# Cing_MainBoard.net
KiCad netlist of a schematic drawn in EAGLE
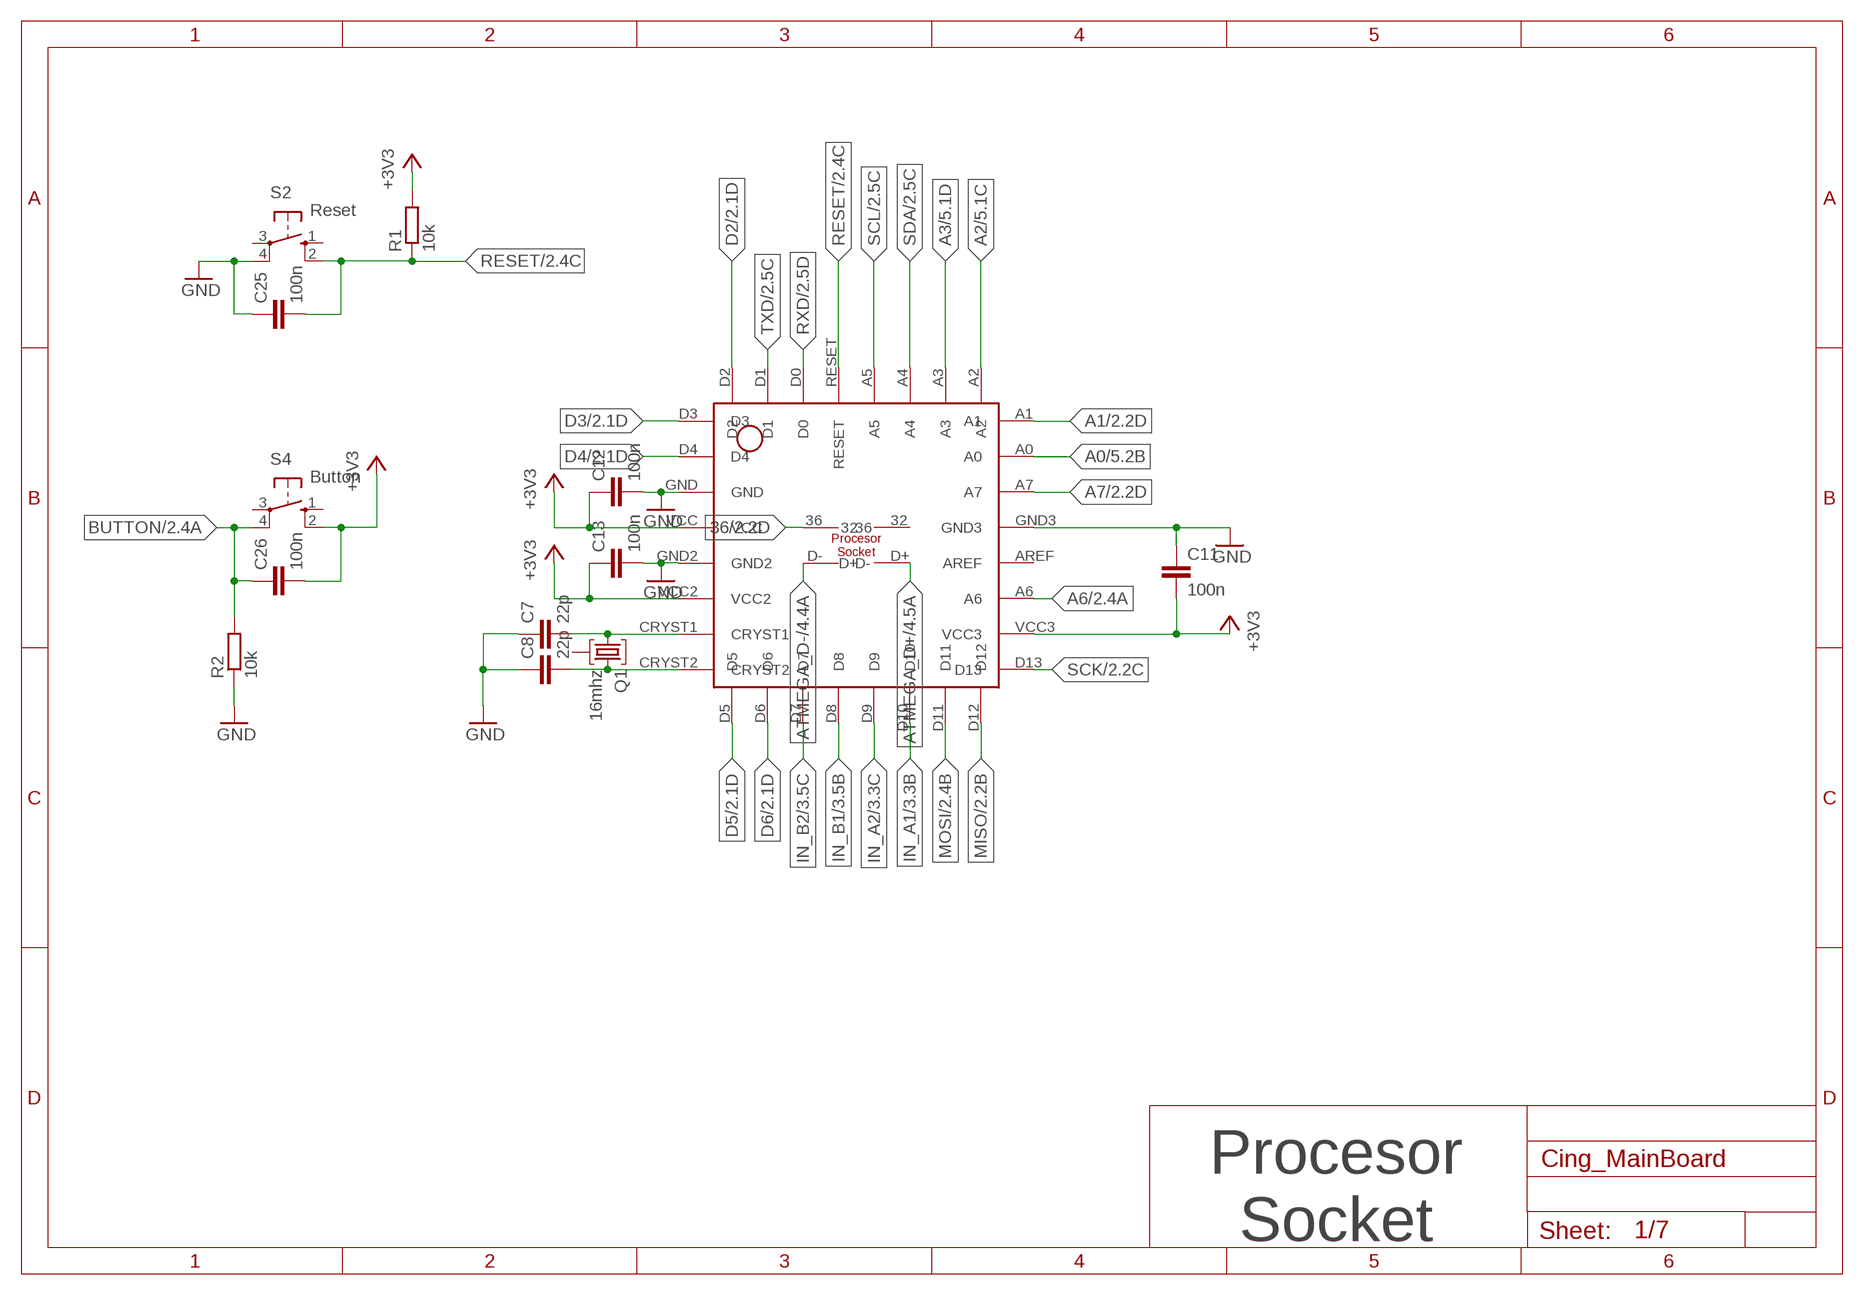
[diagram p0: schematic, sheet 1]
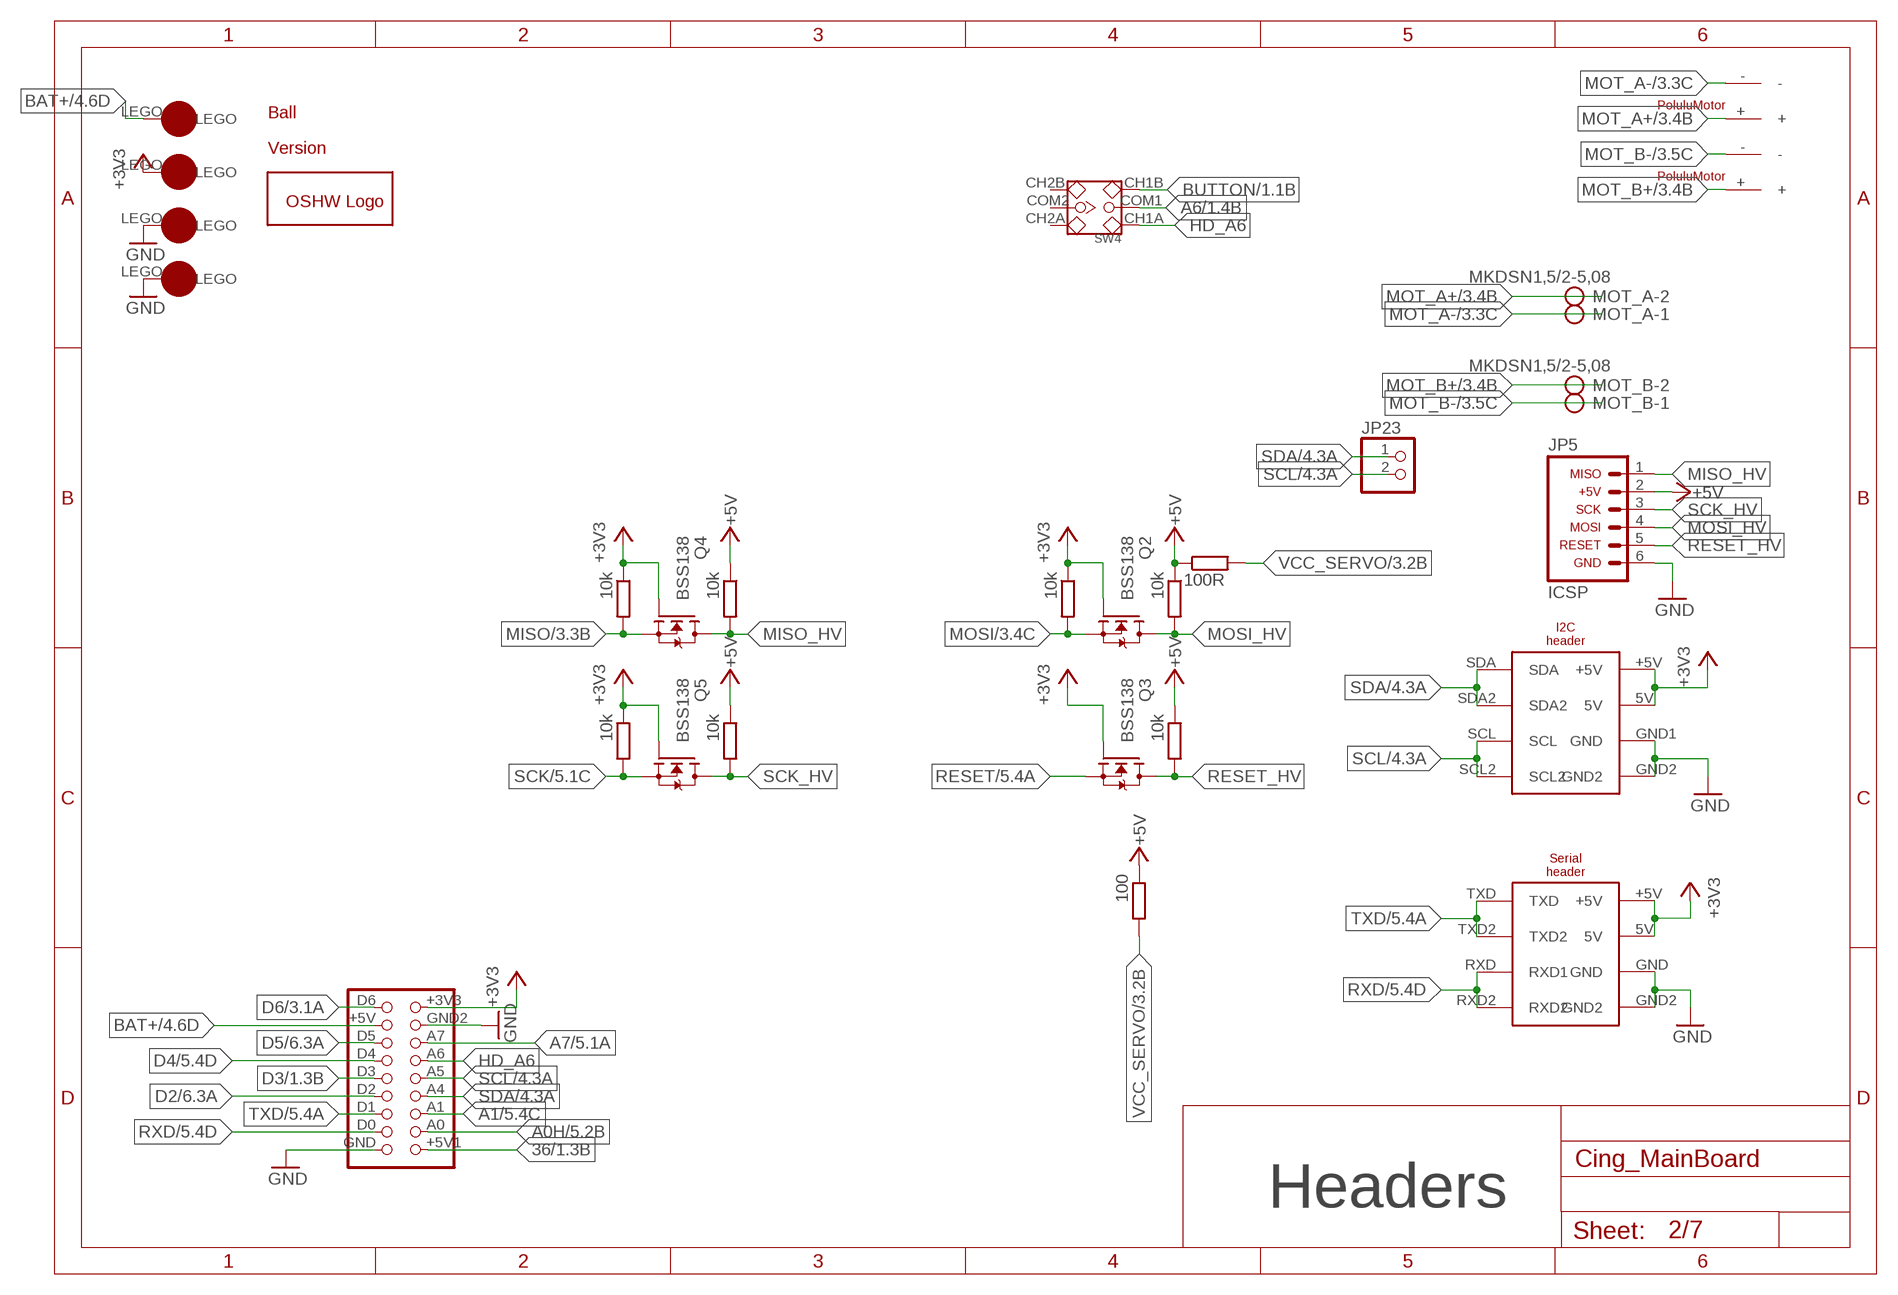
[diagram p1: schematic, sheet 2]
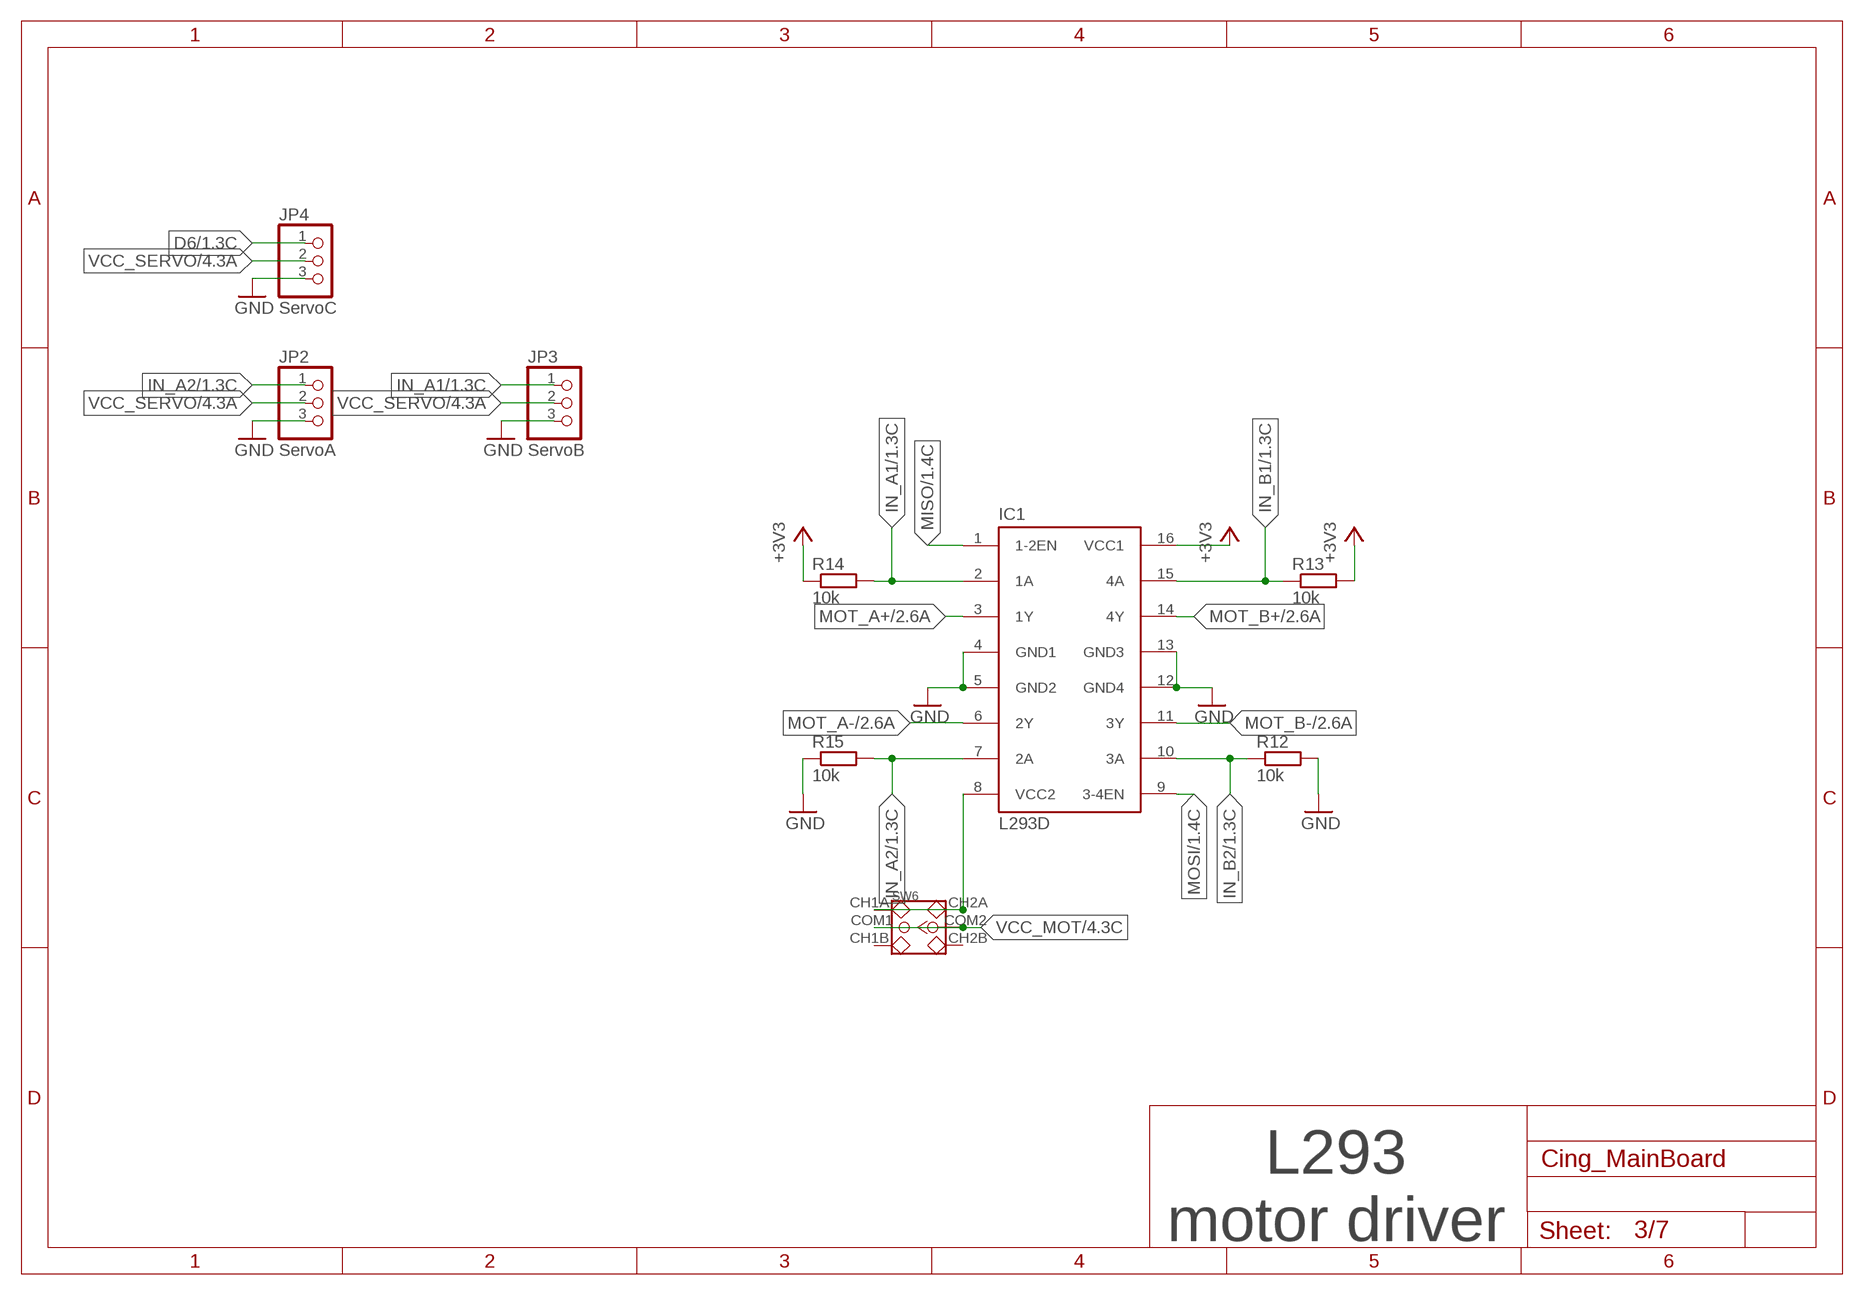
[diagram p2: schematic, sheet 3]
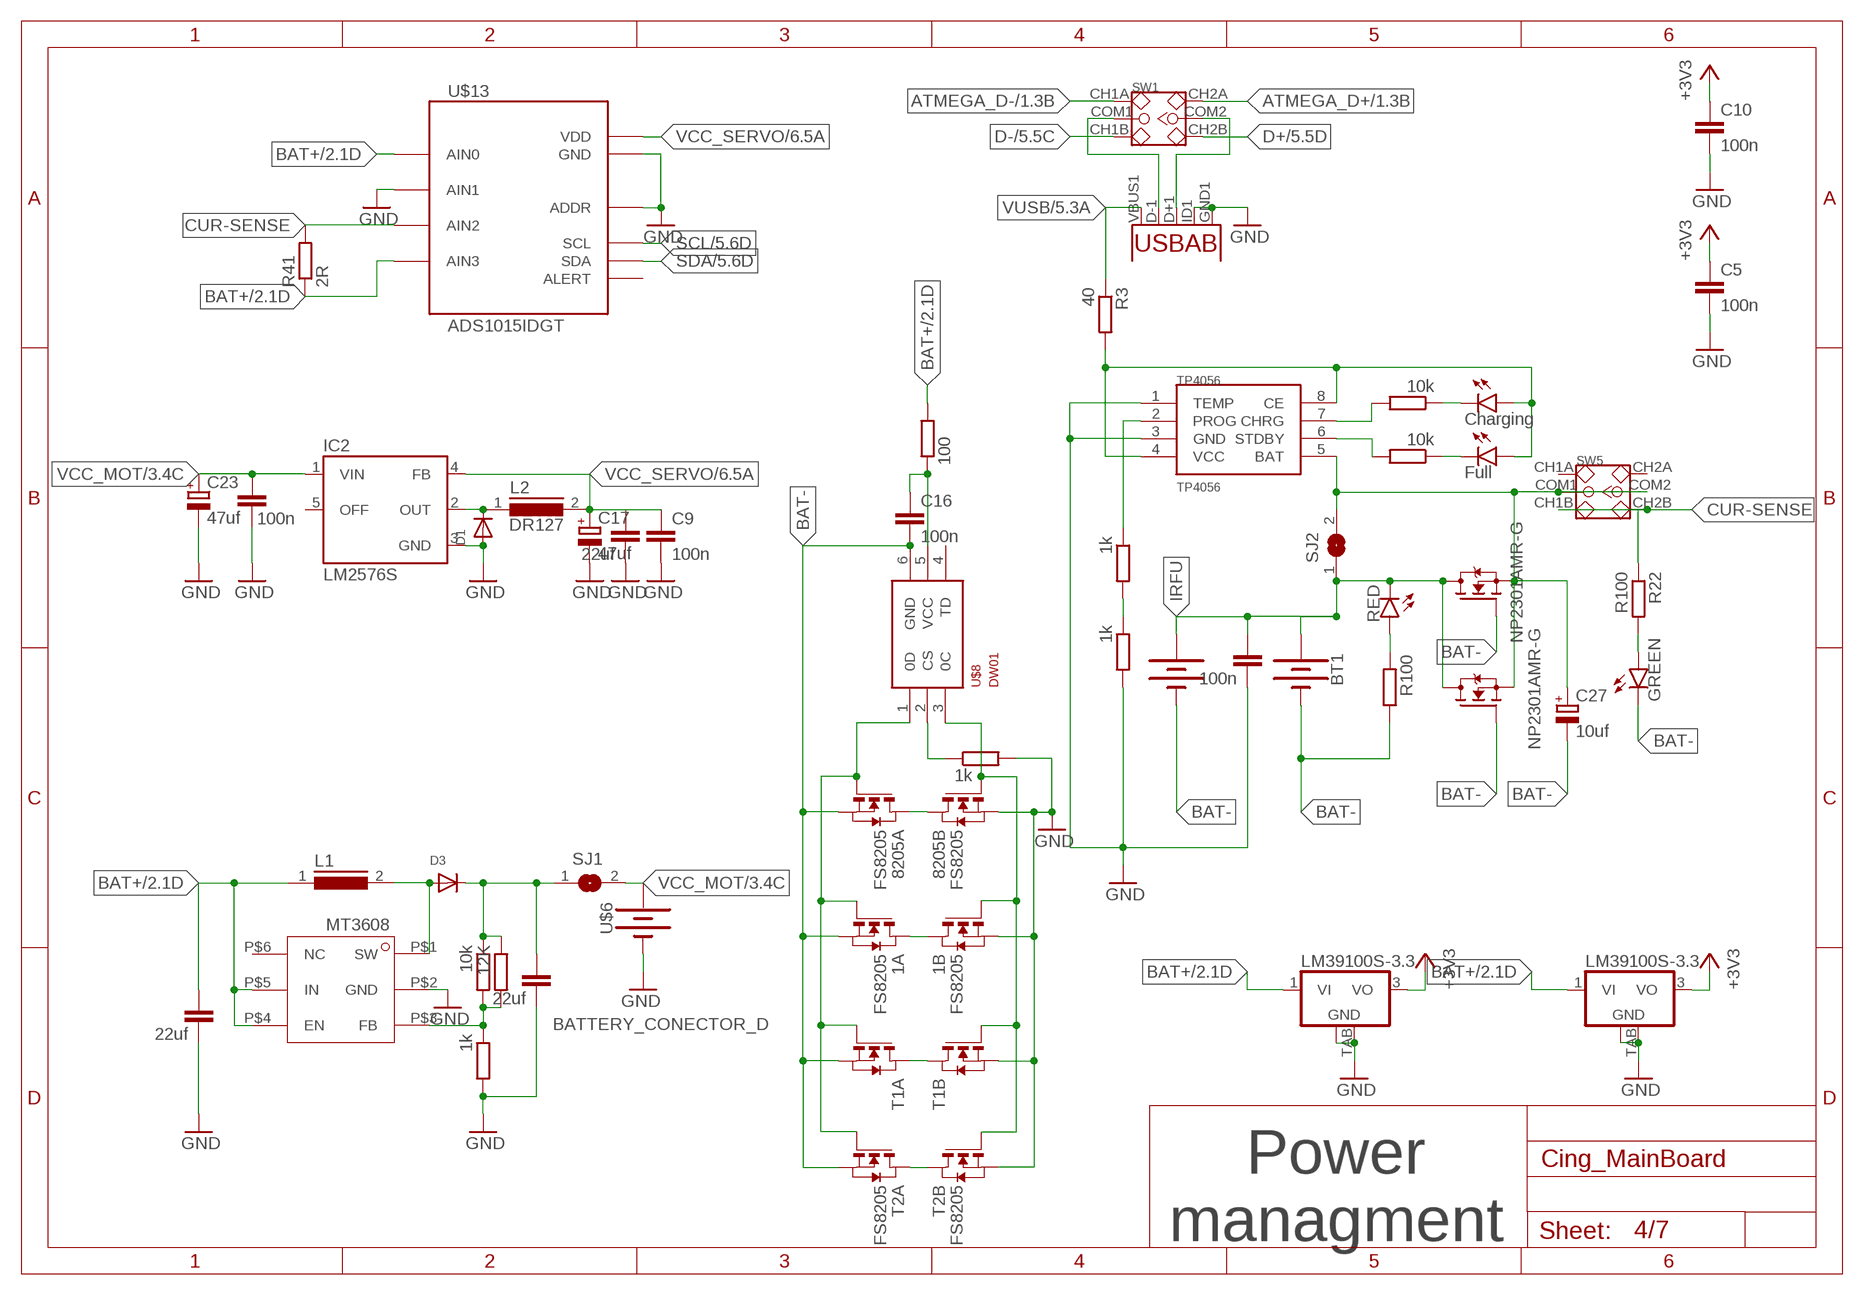
[diagram p3: schematic, sheet 4]
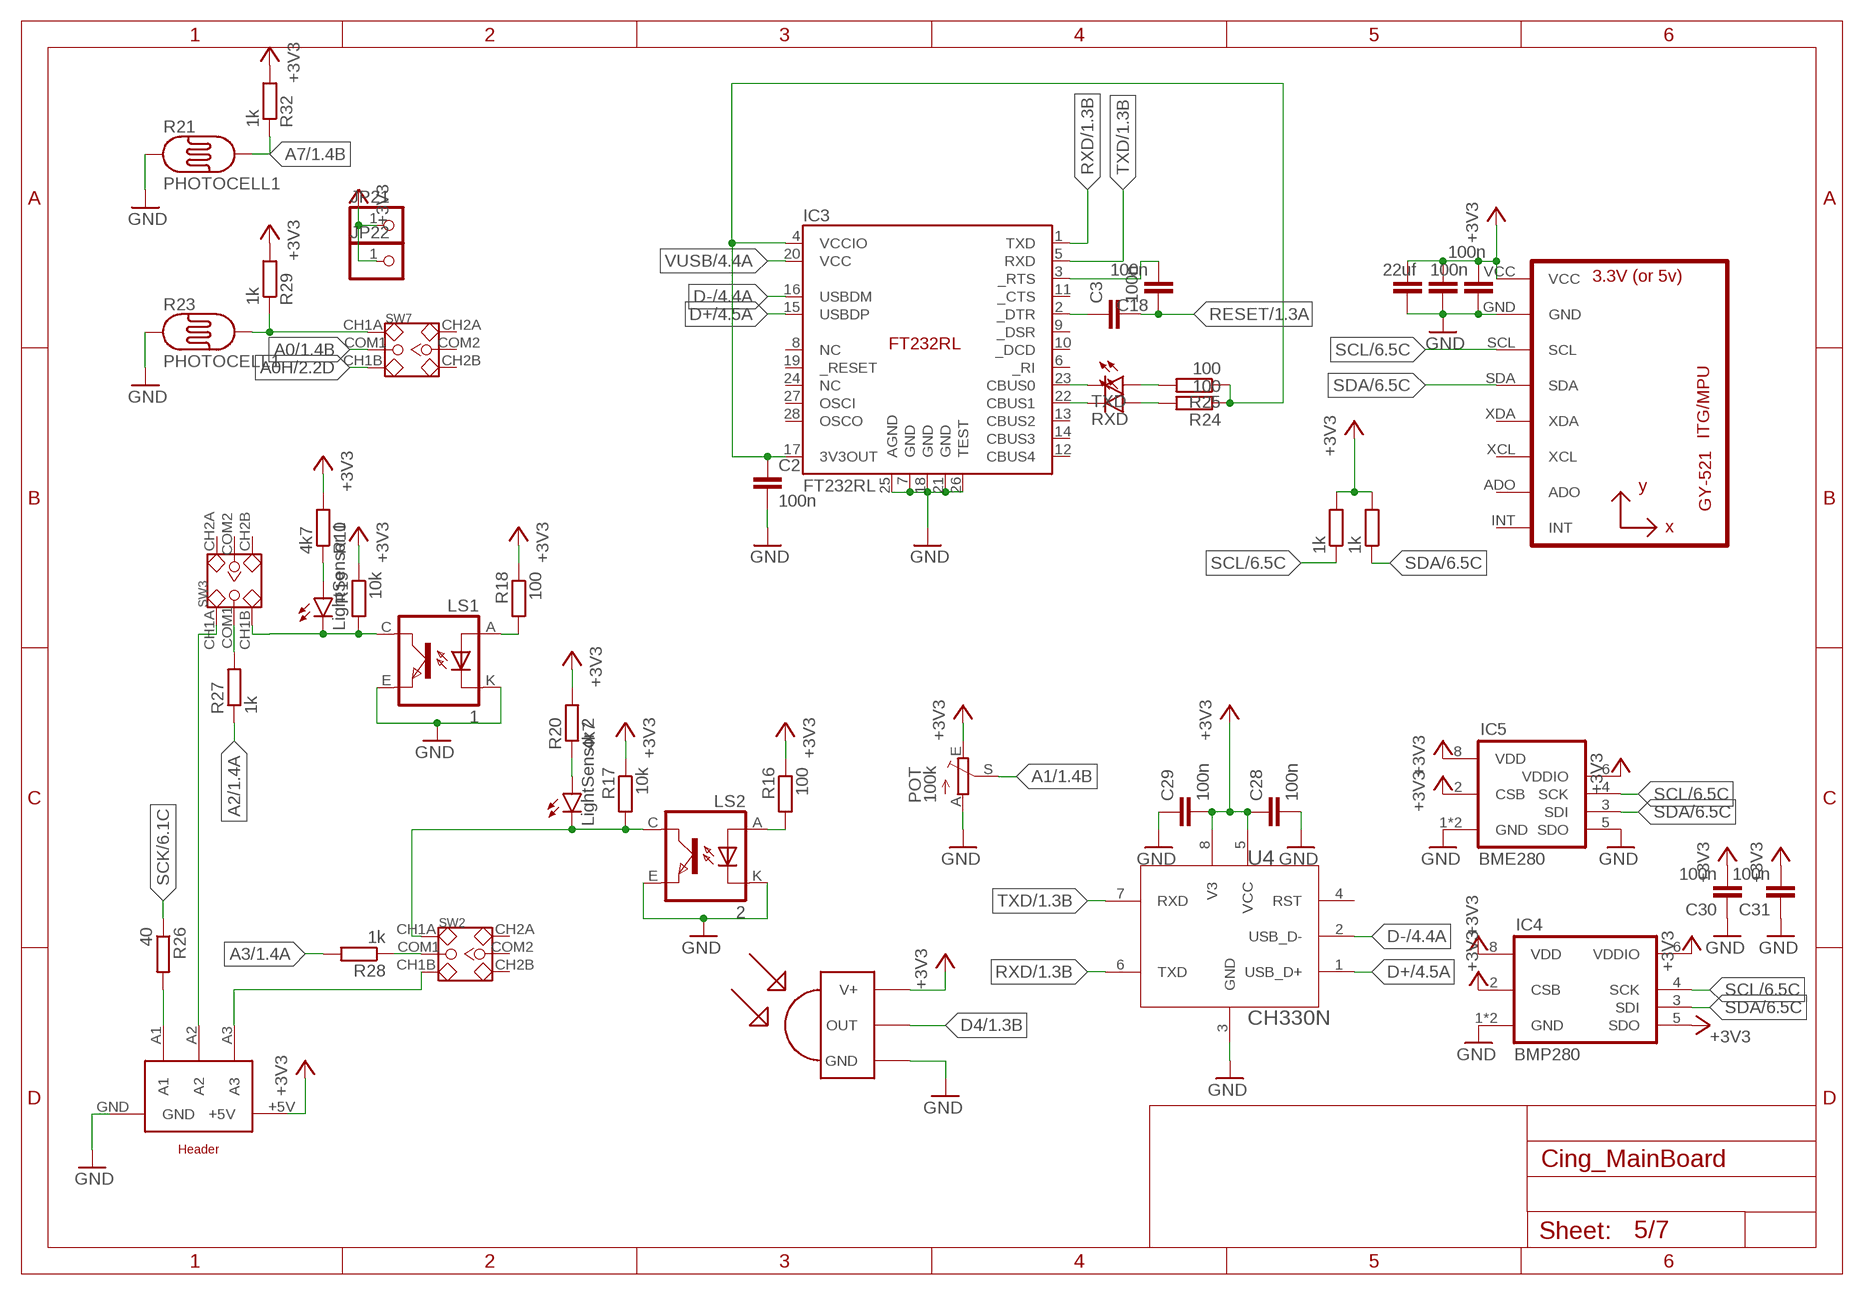
[diagram p4: schematic, sheet 5]
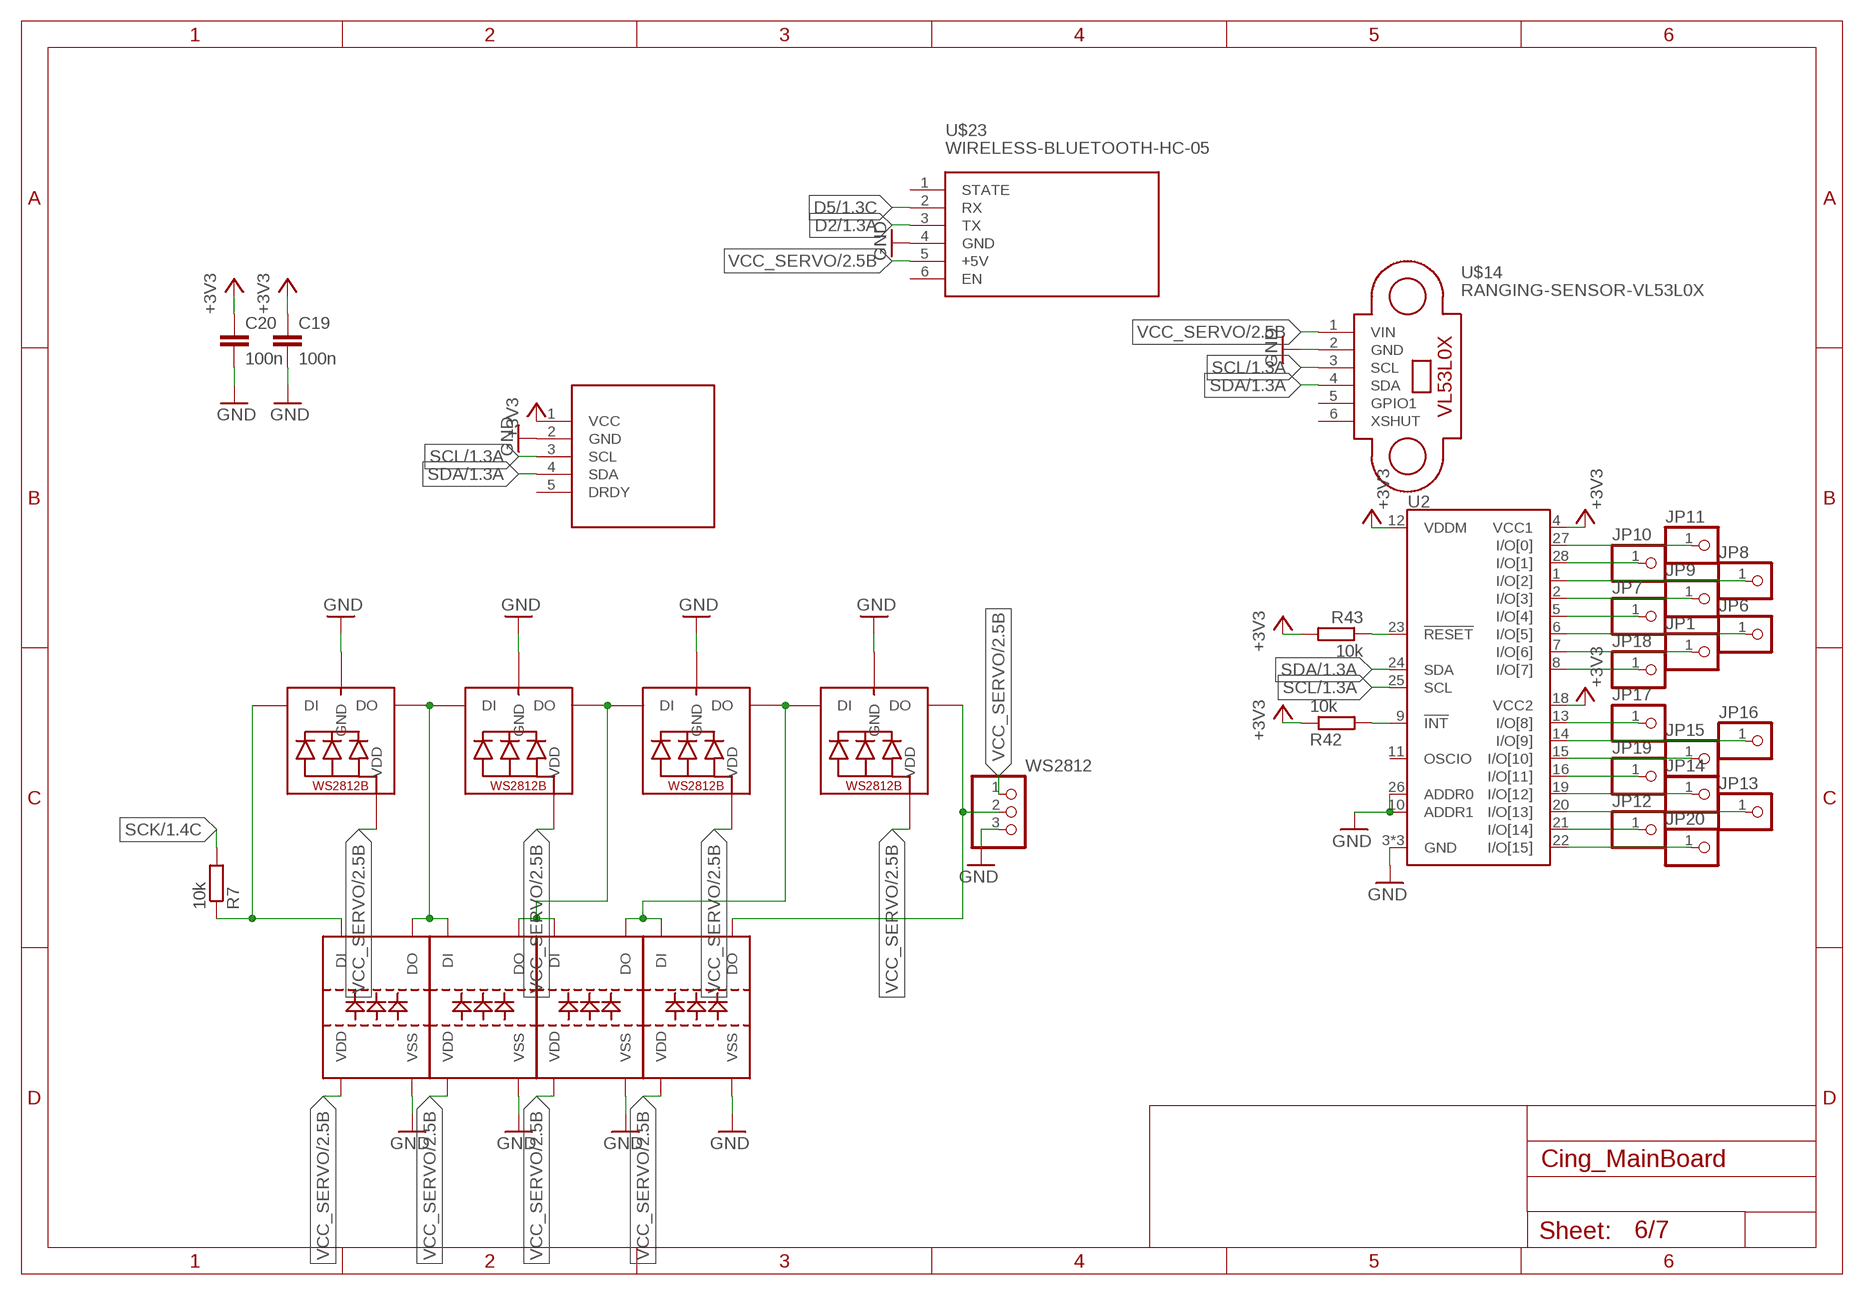
[diagram p5: schematic, sheet 6]
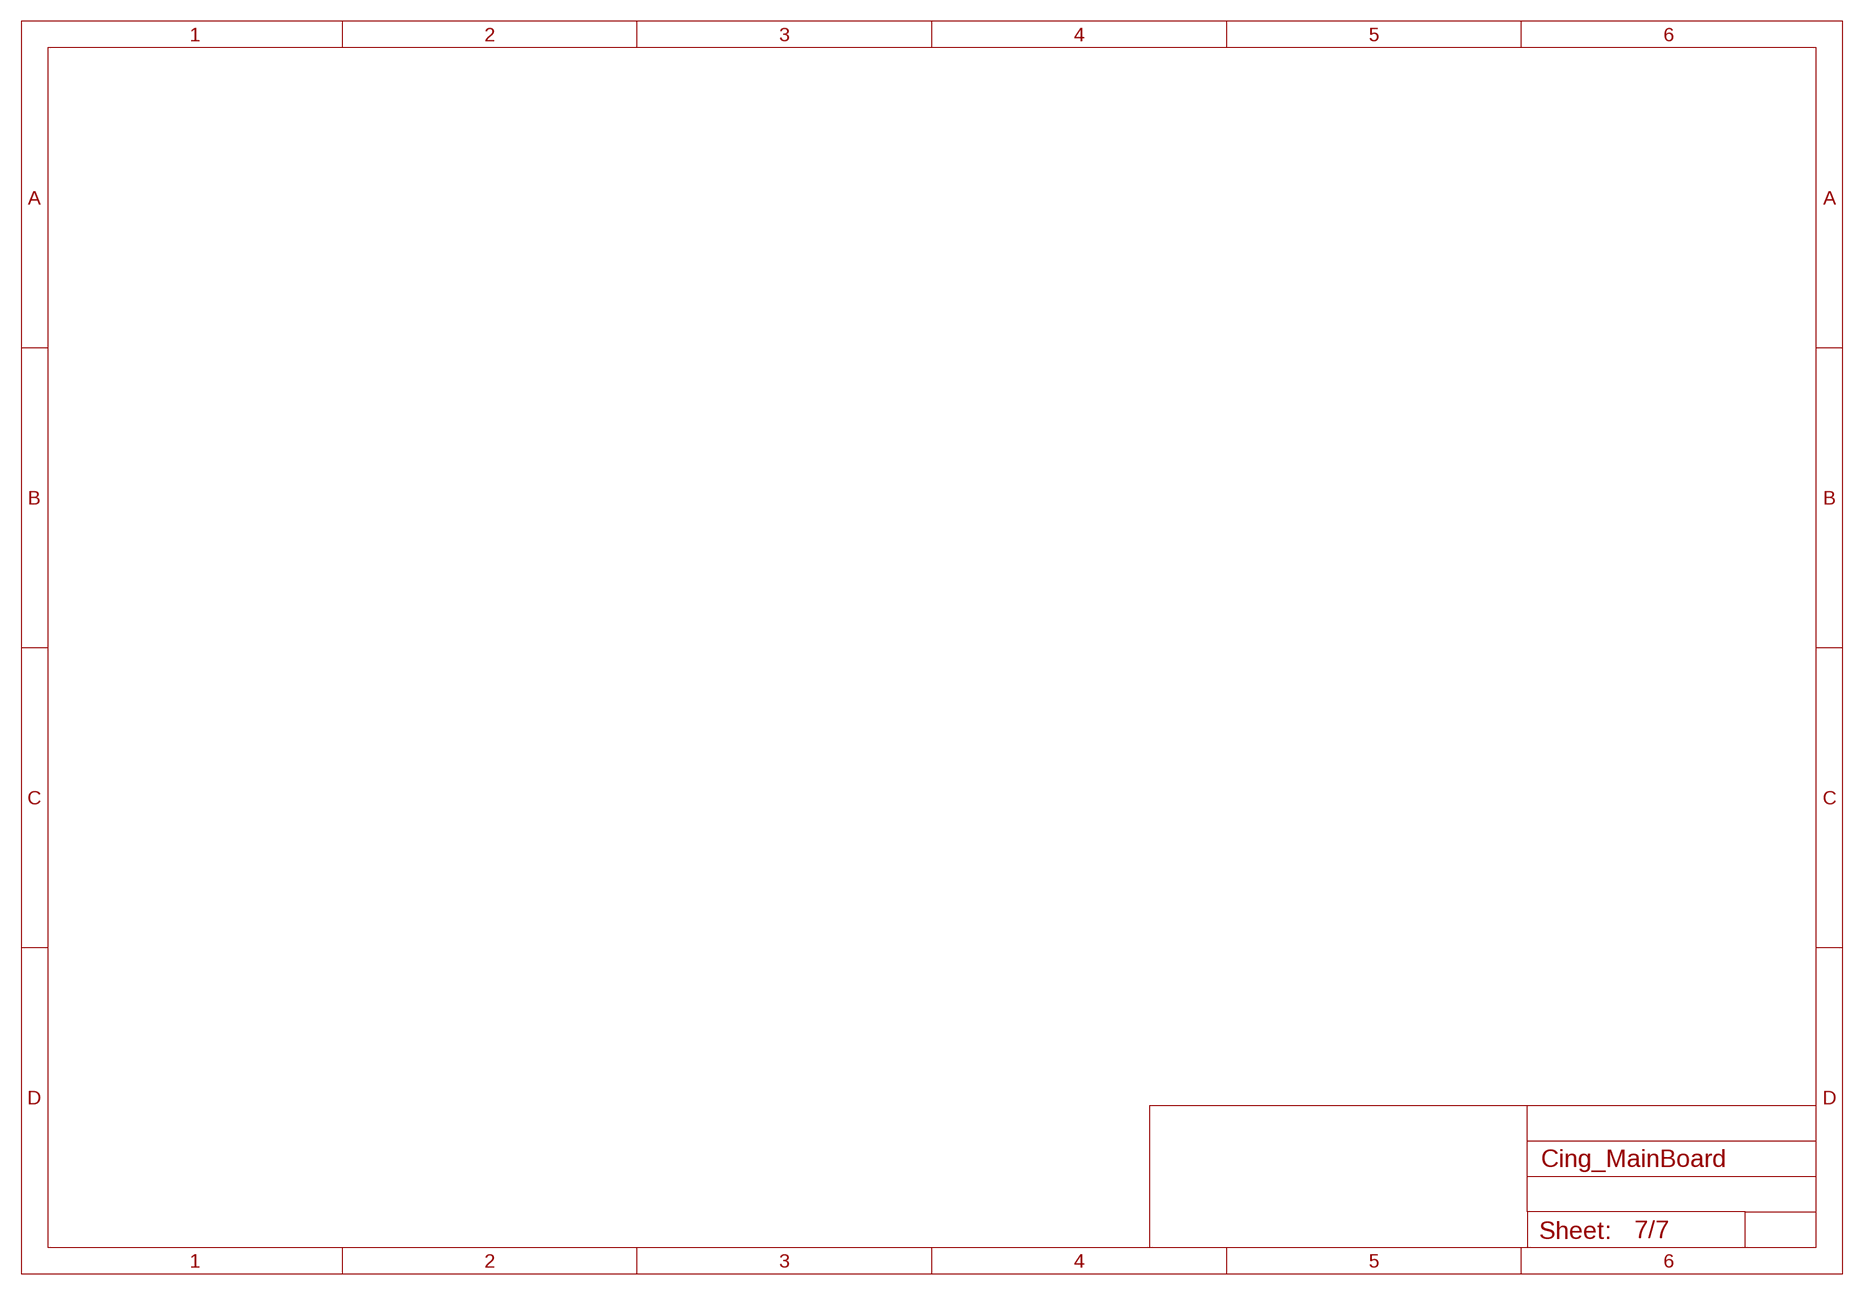
[diagram p6: schematic, sheet 7]

(export (version "E")
  (design (tool "Eeschema 10.0.6"))
  (components
    (comp (ref "C7")
      (value "22p")
      (footprint "eagle-import:C1206")
      (libsource (lib "eagle-import") (part "C-EUC1206"))
    )
    (comp (ref "C8")
      (value "22p")
      (footprint "eagle-import:C1206")
      (libsource (lib "eagle-import") (part "C-EUC1206"))
    )
    (comp (ref "C11")
      (value "100n")
      (footprint "eagle-import:C1206")
      (libsource (lib "eagle-import") (part "C-EUC1206"))
    )
    (comp (ref "C12")
      (value "100n")
      (footprint "eagle-import:C1206")
      (libsource (lib "eagle-import") (part "C-EUC1206"))
    )
    (comp (ref "C13")
      (value "100n")
      (footprint "eagle-import:C1206")
      (libsource (lib "eagle-import") (part "C-EUC1206"))
    )
    (comp (ref "C25")
      (value "100n")
      (footprint "eagle-import:C1206")
      (libsource (lib "eagle-import") (part "C-EUC1206"))
    )
    (comp (ref "C26")
      (value "100n")
      (footprint "eagle-import:C1206")
      (libsource (lib "eagle-import") (part "C-EUC1206"))
    )
    (comp (ref "Q1")
      (value "16mhz")
      (footprint "eagle-import:HC49U")
      (libsource (lib "eagle-import") (part "12M10AHC49HT"))
    )
    (comp (ref "R1")
      (value "10k")
      (footprint "eagle-import:R1206")
      (libsource (lib "eagle-import") (part "R-EU_R1206"))
    )
    (comp (ref "R2")
      (value "10k")
      (footprint "eagle-import:R1206")
      (libsource (lib "eagle-import") (part "R-EU_R1206"))
    )
    (comp (ref "S2")
      (value "Reset")
      (footprint "eagle-import:B3F-10XX")
      (fields (field (name "MPN") "B3F-1000"))
      (libsource (lib "eagle-import") (part "10-XX"))
    )
    (comp (ref "S4")
      (value "Button")
      (footprint "eagle-import:B3F-10XX")
      (fields (field (name "MPN") "B3F-1000"))
      (libsource (lib "eagle-import") (part "10-XX"))
    )
    (comp (ref "U$1")
      (value "PROCESSOR-SOCKET_PCB")
      (footprint "eagle-import:PROCESSOR-SOCKET_PCB")
      (libsource (lib "eagle-import") (part "PROCESSOR-SOCKET_PCB"))
    )
    (comp (ref "C2")
      (value "100n")
      (footprint "eagle-import:C1206")
      (libsource (lib "eagle-import") (part "C-EUC1206"))
    )
    (comp (ref "C3")
      (value "100n")
      (footprint "eagle-import:C1206")
      (libsource (lib "eagle-import") (part "C-EUC1206"))
    )
    (comp (ref "C6")
      (value "100n")
      (footprint "eagle-import:C1206")
      (libsource (lib "eagle-import") (part "C-EUC1206"))
    )
    (comp (ref "C18")
      (value "100n")
      (footprint "eagle-import:C1206")
      (libsource (lib "eagle-import") (part "C-EUC1206"))
    )
    (comp (ref "C21")
      (value "100n")
      (footprint "eagle-import:C1206")
      (libsource (lib "eagle-import") (part "C-EUC1206"))
    )
    (comp (ref "C22")
      (value "22uf")
      (footprint "eagle-import:C1206")
      (libsource (lib "eagle-import") (part "C-EUC1206"))
    )
    (comp (ref "C28")
      (value "100n")
      (footprint "eagle-import:C1206")
      (libsource (lib "eagle-import") (part "C-EUC1206"))
    )
    (comp (ref "C29")
      (value "100n")
      (footprint "eagle-import:C1206")
      (libsource (lib "eagle-import") (part "C-EUC1206"))
    )
    (comp (ref "C30")
      (value "100n")
      (footprint "eagle-import:C1206")
      (libsource (lib "eagle-import") (part "C-EUC1206"))
    )
    (comp (ref "C31")
      (value "100n")
      (footprint "eagle-import:C1206")
      (libsource (lib "eagle-import") (part "C-EUC1206"))
    )
    (comp (ref "IC3")
      (value "FT232RL")
      (footprint "eagle-import:FT232RL")
      (libsource (lib "eagle-import") (part "FT232RL"))
    )
    (comp (ref "IC4")
      (value "BMP280")
      (footprint "eagle-import:BMP280")
      (libsource (lib "eagle-import") (part "BMP280"))
    )
    (comp (ref "IC5")
      (value "BME280")
      (footprint "eagle-import:BME280")
      (libsource (lib "eagle-import") (part "BME280"))
    )
    (comp (ref "JP21")
      (value "PINHD-1X1")
      (footprint "eagle-import:1X01")
      (libsource (lib "eagle-import") (part "PINHD-1X1"))
    )
    (comp (ref "JP22")
      (value "PINHD-1X1")
      (footprint "eagle-import:1X01")
      (libsource (lib "eagle-import") (part "PINHD-1X1"))
    )
    (comp (ref "LED3")
      (value "RXD")
      (footprint "eagle-import:1206")
      (libsource (lib "eagle-import") (part "LEDSMT1206"))
    )
    (comp (ref "LS1")
      (value "1")
      (footprint "eagle-import:TCRT5000")
      (libsource (lib "eagle-import") (part "TCRT5000"))
    )
    (comp (ref "LS2")
      (value "2")
      (footprint "eagle-import:TCRT5000")
      (libsource (lib "eagle-import") (part "TCRT5000"))
    )
    (comp (ref "POT")
      (value "100k")
      (footprint "eagle-import:RJ9W")
      (libsource (lib "eagle-import") (part "TRIM_EU-RJ9W"))
    )
    (comp (ref "R10")
      (value "4k7")
      (footprint "eagle-import:R1206")
      (libsource (lib "eagle-import") (part "R-EU_R1206"))
    )
    (comp (ref "R16")
      (value "100")
      (footprint "eagle-import:R1206")
      (libsource (lib "eagle-import") (part "R-EU_R1206"))
    )
    (comp (ref "R17")
      (value "10k")
      (footprint "eagle-import:R1206")
      (libsource (lib "eagle-import") (part "R-EU_R1206"))
    )
    (comp (ref "R18")
      (value "100")
      (footprint "eagle-import:R1206")
      (libsource (lib "eagle-import") (part "R-EU_R1206"))
    )
    (comp (ref "R19")
      (value "10k")
      (footprint "eagle-import:R1206")
      (libsource (lib "eagle-import") (part "R-EU_R1206"))
    )
    (comp (ref "R20")
      (value "4k7")
      (footprint "eagle-import:R1206")
      (libsource (lib "eagle-import") (part "R-EU_R1206"))
    )
    (comp (ref "R21")
      (value "PHOTOCELL1")
      (footprint "eagle-import:LDR_OFFBOARD")
      (libsource (lib "eagle-import") (part "PHOTOCELL1"))
    )
    (comp (ref "R23")
      (value "PHOTOCELL1")
      (footprint "eagle-import:LDR_OFFBOARD")
      (libsource (lib "eagle-import") (part "PHOTOCELL1"))
    )
    (comp (ref "R24")
      (value "100")
      (footprint "eagle-import:R1206")
      (libsource (lib "eagle-import") (part "R-EU_R1206"))
    )
    (comp (ref "R25")
      (value "100")
      (footprint "eagle-import:R1206")
      (libsource (lib "eagle-import") (part "R-EU_R1206"))
    )
    (comp (ref "R26")
      (value "40")
      (footprint "eagle-import:R1206")
      (libsource (lib "eagle-import") (part "R-EU_R1206"))
    )
    (comp (ref "R27")
      (value "1k")
      (footprint "eagle-import:R1206")
      (libsource (lib "eagle-import") (part "R-EU_R1206"))
    )
    (comp (ref "R28")
      (value "1k")
      (footprint "eagle-import:R1206")
      (libsource (lib "eagle-import") (part "R-EU_R1206"))
    )
    (comp (ref "R29")
      (value "1k")
      (footprint "eagle-import:R1206")
      (libsource (lib "eagle-import") (part "R-EU_R1206"))
    )
    (comp (ref "R30")
      (value "1k")
      (footprint "eagle-import:R1206")
      (libsource (lib "eagle-import") (part "R-EU_R1206"))
    )
    (comp (ref "R31")
      (value "1k")
      (footprint "eagle-import:R1206")
      (libsource (lib "eagle-import") (part "R-EU_R1206"))
    )
    (comp (ref "R32")
      (value "1k")
      (footprint "eagle-import:R1206")
      (libsource (lib "eagle-import") (part "R-EU_R1206"))
    )
    (comp (ref "SW2")
      (value "USB_SWITCH")
      (footprint "eagle-import:USB_SWITCH")
      (libsource (lib "eagle-import") (part "USB_SWITCH"))
    )
    (comp (ref "SW3")
      (value "USB_SWITCH")
      (footprint "eagle-import:USB_SWITCH")
      (libsource (lib "eagle-import") (part "USB_SWITCH"))
    )
    (comp (ref "SW7")
      (value "USB_SWITCH")
      (footprint "eagle-import:USB_SWITCH")
      (libsource (lib "eagle-import") (part "USB_SWITCH"))
    )
    (comp (ref "TSOP4838")
      (value "TSOP4838")
      (footprint "eagle-import:TSOP18XX")
      (libsource (lib "eagle-import") (part "TSOP4838"))
    )
    (comp (ref "TXD")
      (value "TXD")
      (footprint "eagle-import:1206")
      (libsource (lib "eagle-import") (part "LEDSMT1206"))
    )
    (comp (ref "TXD1")
      (value "LightSensor 1")
      (footprint "eagle-import:1206")
      (libsource (lib "eagle-import") (part "LEDSMT1206"))
    )
    (comp (ref "TXD2")
      (value "LightSensor 2")
      (footprint "eagle-import:1206")
      (libsource (lib "eagle-import") (part "LEDSMT1206"))
    )
    (comp (ref "U$12")
      (value "CONNECTOR_1X5")
      (footprint "eagle-import:CONNECTOR_1X5")
      (libsource (lib "eagle-import") (part "CONNECTOR_1X5"))
    )
    (comp (ref "U3")
      (value "MPU-6050MPU6050")
      (footprint "eagle-import:MPU-6050")
      (libsource (lib "eagle-import") (part "MPU-6050MPU6050"))
    )
    (comp (ref "U4")
      (value "CH330N")
      (footprint "eagle-import:SOIC-8N")
      (fields
        (field (name "DIGI-KEY_PART") "LM555CMFS-ND")
        (field (name "MANUFACTURER") "ON Semiconductor")
        (field (name "MPN") "LM555CM")
        (field (name "CREATED_BY") "PCBLayout.com")
      )
      (libsource (lib "eagle-import") (part "CH330N"))
    )
    (comp (ref "1")
      (value "FS8205")
      (footprint "eagle-import:TSSOP-8")
      (libsource (lib "eagle-import") (part "DMN3024LSD"))
    )
    (comp (ref "8205")
      (value "FS8205")
      (footprint "eagle-import:TSSOP-8")
      (libsource (lib "eagle-import") (part "DMN3024LSD"))
    )
    (comp (ref "BT1")
      (value "BATTERY-AA_KIT")
      (footprint "eagle-import:BATTERY-AA-KIT")
      (libsource (lib "eagle-import") (part "BATTERY-AA_KIT"))
    )
    (comp (ref "C1")
      (value "100n")
      (footprint "eagle-import:C1206")
      (libsource (lib "eagle-import") (part "C-EUC1206"))
    )
    (comp (ref "C4")
      (value "22uf")
      (footprint "eagle-import:C1206")
      (libsource (lib "eagle-import") (part "C-EUC1206"))
    )
    (comp (ref "C5")
      (value "100n")
      (footprint "eagle-import:C1206")
      (libsource (lib "eagle-import") (part "C-EUC1206"))
    )
    (comp (ref "C9")
      (value "100n")
      (footprint "eagle-import:C1206")
      (libsource (lib "eagle-import") (part "C-EUC1206"))
    )
    (comp (ref "C10")
      (value "100n")
      (footprint "eagle-import:C1206")
      (libsource (lib "eagle-import") (part "C-EUC1206"))
    )
    (comp (ref "C14")
      (value "22uf")
      (footprint "eagle-import:C1206")
      (libsource (lib "eagle-import") (part "C-EUC1206"))
    )
    (comp (ref "C15")
      (value "22uf")
      (footprint "eagle-import:C1206")
      (libsource (lib "eagle-import") (part "C-EUC1206"))
    )
    (comp (ref "C16")
      (value "100n")
      (footprint "eagle-import:C1206")
      (libsource (lib "eagle-import") (part "C-EUC1206"))
    )
    (comp (ref "C17")
      (value "47uf")
      (footprint "eagle-import:153CLV-0505")
      (libsource (lib "eagle-import") (part "CPOL-EU153CLV-0505"))
    )
    (comp (ref "C23")
      (value "47uf")
      (footprint "eagle-import:153CLV-0505")
      (libsource (lib "eagle-import") (part "CPOL-EU153CLV-0505"))
    )
    (comp (ref "C24")
      (value "100n")
      (footprint "eagle-import:C1206")
      (libsource (lib "eagle-import") (part "C-EUC1206"))
    )
    (comp (ref "C27")
      (value "10uf")
      (footprint "eagle-import:153CLV-0505")
      (libsource (lib "eagle-import") (part "CPOL-EU153CLV-0505"))
    )
    (comp (ref "D1")
      (value "DIODESMA")
      (footprint "eagle-import:SMADIODE")
      (libsource (lib "eagle-import") (part "DIODESMA"))
    )
    (comp (ref "D3")
      (value "DIODESMA")
      (footprint "eagle-import:SMADIODE")
      (libsource (lib "eagle-import") (part "DIODESMA"))
    )
    (comp (ref "IC2")
      (value "LM2576S")
      (footprint "eagle-import:TO263-5")
      (libsource (lib "eagle-import") (part "LM2576S"))
    )
    (comp (ref "L1")
      (value "DR125")
      (footprint "eagle-import:DR125")
      (libsource (lib "eagle-import") (part "DR125"))
    )
    (comp (ref "L2")
      (value "DR127")
      (footprint "eagle-import:DR127")
      (libsource (lib "eagle-import") (part "DR127"))
    )
    (comp (ref "LED1")
      (value "Charging")
      (footprint "eagle-import:1206")
      (libsource (lib "eagle-import") (part "LEDSMT1206"))
    )
    (comp (ref "ON")
      (value "GREEN")
      (footprint "eagle-import:1206")
      (libsource (lib "eagle-import") (part "LEDSMT1206"))
    )
    (comp (ref "Q6")
      (value "NP2301AMR-G")
      (footprint "eagle-import:SOT23")
      (fields (field (name "MF") "Fairchild") (field (name "MPN") "BSS138"))
      (libsource (lib "eagle-import") (part "NP2301AMR-G"))
    )
    (comp (ref "Q7")
      (value "NP2301AMR-G")
      (footprint "eagle-import:SOT23")
      (fields (field (name "MF") "Fairchild") (field (name "MPN") "BSS138"))
      (libsource (lib "eagle-import") (part "NP2301AMR-G"))
    )
    (comp (ref "R3")
      (value "40")
      (footprint "eagle-import:R1206")
      (libsource (lib "eagle-import") (part "R-EU_R1206"))
    )
    (comp (ref "R4")
      (value "1k")
      (footprint "eagle-import:R1206")
      (libsource (lib "eagle-import") (part "R-EU_R1206"))
    )
    (comp (ref "R5")
      (value "10k")
      (footprint "eagle-import:R1206")
      (libsource (lib "eagle-import") (part "R-EU_R1206"))
    )
    (comp (ref "R6")
      (value "R100")
      (footprint "eagle-import:R1206")
      (libsource (lib "eagle-import") (part "R-EU_R1206"))
    )
    (comp (ref "R8")
      (value "1k")
      (footprint "eagle-import:R1206")
      (libsource (lib "eagle-import") (part "R-EU_R1206"))
    )
    (comp (ref "R9")
      (value "10k")
      (footprint "eagle-import:R1206")
      (libsource (lib "eagle-import") (part "R-EU_R1206"))
    )
    (comp (ref "R11")
      (value "10k")
      (footprint "eagle-import:R1206")
      (libsource (lib "eagle-import") (part "R-EU_R1206"))
    )
    (comp (ref "R22")
      (value "R100")
      (footprint "eagle-import:R1206")
      (libsource (lib "eagle-import") (part "R-EU_R1206"))
    )
    (comp (ref "R41")
      (value "2R")
      (footprint "eagle-import:R1206")
      (libsource (lib "eagle-import") (part "R-EU_R1206"))
    )
    (comp (ref "R46")
      (value "1k")
      (footprint "eagle-import:R1206")
      (libsource (lib "eagle-import") (part "R-EU_R1206"))
    )
    (comp (ref "R47")
      (value "1k")
      (footprint "eagle-import:R1206")
      (libsource (lib "eagle-import") (part "R-EU_R1206"))
    )
    (comp (ref "R48")
      (value "100")
      (footprint "eagle-import:R1206")
      (libsource (lib "eagle-import") (part "R-EU_R1206"))
    )
    (comp (ref "R49")
      (value "12K")
      (footprint "eagle-import:R1206")
      (libsource (lib "eagle-import") (part "R-EU_R1206"))
    )
    (comp (ref "REV")
      (value "RED")
      (footprint "eagle-import:1206")
      (libsource (lib "eagle-import") (part "LEDSMT1206"))
    )
    (comp (ref "SJ1")
      (value "SJW")
      (footprint "eagle-import:SJW")
      (libsource (lib "eagle-import") (part "SJW"))
    )
    (comp (ref "SJ2") (value "SJ") (footprint "eagle-import:SJ") (libsource (lib "eagle-import") (part "SJ")))
    (comp (ref "SW1")
      (value "USB_SWITCH")
      (footprint "eagle-import:USB_SWITCH")
      (libsource (lib "eagle-import") (part "USB_SWITCH"))
    )
    (comp (ref "SW5")
      (value "USB_SWITCH")
      (footprint "eagle-import:USB_SWITCH")
      (libsource (lib "eagle-import") (part "USB_SWITCH"))
    )
    (comp (ref "T1")
      (value "FS8205")
      (footprint "eagle-import:TSSOP-8")
      (libsource (lib "eagle-import") (part "DMN3024LSD"))
    )
    (comp (ref "T2")
      (value "FS8205")
      (footprint "eagle-import:TSSOP-8")
      (libsource (lib "eagle-import") (part "DMN3024LSD"))
    )
    (comp (ref "TP4056")
      (value "TP4056")
      (footprint "eagle-import:TP4056")
      (libsource (lib "eagle-import") (part "TP4056"))
    )
    (comp (ref "U$5")
      (value "MT3608SOT23-6")
      (footprint "eagle-import:SOT23-6")
      (libsource (lib "eagle-import") (part "MT3608SOT23-6"))
    )
    (comp (ref "U$6")
      (value "BATTERY_CONECTOR_D")
      (footprint "eagle-import:BATTERY_CONECTOR_D")
      (libsource (lib "eagle-import") (part "BATTERY_CONECTOR_D"))
    )
    (comp (ref "U$7")
      (value "BATTERY_CONECTOR_D")
      (footprint "eagle-import:BATTERY_CONECTOR_D")
      (libsource (lib "eagle-import") (part "BATTERY_CONECTOR_D"))
    )
    (comp (ref "U$8")
      (value "DW01")
      (footprint "eagle-import:SOT23-6")
      (libsource (lib "eagle-import") (part "DW01"))
    )
    (comp (ref "U$13")
      (value "ADS1015IDGT")
      (footprint "eagle-import:MSOP10_0.5")
      (libsource (lib "eagle-import") (part "ADS1015IDGT"))
    )
    (comp (ref "U$25")
      (value "LM39100S-3.3")
      (footprint "eagle-import:LM39100S-3.3")
      (libsource (lib "eagle-import") (part "LM39100S-3.3"))
    )
    (comp (ref "U$26")
      (value "LM39100S-3.3")
      (footprint "eagle-import:LM39100S-3.3")
      (libsource (lib "eagle-import") (part "LM39100S-3.3"))
    )
    (comp (ref "U1")
      (value "MICRO_USB\"\"")
      (footprint "eagle-import:USB-MICRO-SMD")
      (libsource (lib "eagle-import") (part "MICRO_USB{dblquote}{dblquote}"))
    )
    (comp (ref "YELLOW")
      (value "Full")
      (footprint "eagle-import:1206")
      (libsource (lib "eagle-import") (part "LEDSMT1206"))
    )
    (comp (ref "C19")
      (value "100n")
      (footprint "eagle-import:C1206")
      (libsource (lib "eagle-import") (part "C-EUC1206"))
    )
    (comp (ref "C20")
      (value "100n")
      (footprint "eagle-import:C1206")
      (libsource (lib "eagle-import") (part "C-EUC1206"))
    )
    (comp (ref "JP1")
      (value "PINHD-1X1")
      (footprint "eagle-import:1X01")
      (libsource (lib "eagle-import") (part "PINHD-1X1"))
    )
    (comp (ref "JP6")
      (value "PINHD-1X1")
      (footprint "eagle-import:1X01")
      (libsource (lib "eagle-import") (part "PINHD-1X1"))
    )
    (comp (ref "JP7")
      (value "PINHD-1X1")
      (footprint "eagle-import:1X01")
      (libsource (lib "eagle-import") (part "PINHD-1X1"))
    )
    (comp (ref "JP8")
      (value "PINHD-1X1")
      (footprint "eagle-import:1X01")
      (libsource (lib "eagle-import") (part "PINHD-1X1"))
    )
    (comp (ref "JP9")
      (value "PINHD-1X1")
      (footprint "eagle-import:1X01")
      (libsource (lib "eagle-import") (part "PINHD-1X1"))
    )
    (comp (ref "JP10")
      (value "PINHD-1X1")
      (footprint "eagle-import:1X01")
      (libsource (lib "eagle-import") (part "PINHD-1X1"))
    )
    (comp (ref "JP11")
      (value "PINHD-1X1")
      (footprint "eagle-import:1X01")
      (libsource (lib "eagle-import") (part "PINHD-1X1"))
    )
    (comp (ref "JP12")
      (value "PINHD-1X1")
      (footprint "eagle-import:1X01")
      (libsource (lib "eagle-import") (part "PINHD-1X1"))
    )
    (comp (ref "JP13")
      (value "PINHD-1X1")
      (footprint "eagle-import:1X01")
      (libsource (lib "eagle-import") (part "PINHD-1X1"))
    )
    (comp (ref "JP14")
      (value "PINHD-1X1")
      (footprint "eagle-import:1X01")
      (libsource (lib "eagle-import") (part "PINHD-1X1"))
    )
    (comp (ref "JP15")
      (value "PINHD-1X1")
      (footprint "eagle-import:1X01")
      (libsource (lib "eagle-import") (part "PINHD-1X1"))
    )
    (comp (ref "JP16")
      (value "PINHD-1X1")
      (footprint "eagle-import:1X01")
      (libsource (lib "eagle-import") (part "PINHD-1X1"))
    )
    (comp (ref "JP17")
      (value "PINHD-1X1")
      (footprint "eagle-import:1X01")
      (libsource (lib "eagle-import") (part "PINHD-1X1"))
    )
    (comp (ref "JP18")
      (value "PINHD-1X1")
      (footprint "eagle-import:1X01")
      (libsource (lib "eagle-import") (part "PINHD-1X1"))
    )
    (comp (ref "JP19")
      (value "PINHD-1X1")
      (footprint "eagle-import:1X01")
      (libsource (lib "eagle-import") (part "PINHD-1X1"))
    )
    (comp (ref "JP20")
      (value "PINHD-1X1")
      (footprint "eagle-import:1X01")
      (libsource (lib "eagle-import") (part "PINHD-1X1"))
    )
    (comp (ref "LED4")
      (value "WS2812B3535")
      (footprint "eagle-import:LED3535")
      (libsource (lib "eagle-import") (part "WS2812B3535"))
    )
    (comp (ref "LED5")
      (value "WS2812B")
      (footprint "eagle-import:WS2812B")
      (libsource (lib "eagle-import") (part "WS2812B"))
    )
    (comp (ref "LED6")
      (value "WS2812B")
      (footprint "eagle-import:WS2812B")
      (libsource (lib "eagle-import") (part "WS2812B"))
    )
    (comp (ref "LED7")
      (value "WS2812B")
      (footprint "eagle-import:WS2812B")
      (libsource (lib "eagle-import") (part "WS2812B"))
    )
    (comp (ref "LED8")
      (value "WS2812B")
      (footprint "eagle-import:WS2812B")
      (libsource (lib "eagle-import") (part "WS2812B"))
    )
    (comp (ref "LED9")
      (value "WS2812B3535")
      (footprint "eagle-import:LED3535")
      (libsource (lib "eagle-import") (part "WS2812B3535"))
    )
    (comp (ref "LED10")
      (value "WS2812B3535")
      (footprint "eagle-import:LED3535")
      (libsource (lib "eagle-import") (part "WS2812B3535"))
    )
    (comp (ref "LED11")
      (value "WS2812B3535")
      (footprint "eagle-import:LED3535")
      (libsource (lib "eagle-import") (part "WS2812B3535"))
    )
    (comp (ref "R7")
      (value "10k")
      (footprint "eagle-import:R1206")
      (libsource (lib "eagle-import") (part "R-EU_R1206"))
    )
    (comp (ref "R42")
      (value "10k")
      (footprint "eagle-import:R1206")
      (libsource (lib "eagle-import") (part "R-EU_R1206"))
    )
    (comp (ref "R43")
      (value "10k")
      (footprint "eagle-import:R1206")
      (libsource (lib "eagle-import") (part "R-EU_R1206"))
    )
    (comp (ref "U$14")
      (value "RANGING-SENSOR-VL53L0X")
      (footprint "eagle-import:RANGING-SENSOR-VL53L0X")
      (libsource (lib "eagle-import") (part "RANGING-SENSOR-VL53L0X"))
    )
    (comp (ref "U$15")
      (value "COMPASS-HMC5883L")
      (footprint "eagle-import:COMPASS-HMC5883L")
      (libsource (lib "eagle-import") (part "COMPASS-HMC5883L"))
    )
    (comp (ref "U$23")
      (value "WIRELESS-BLUETOOTH-HC-05")
      (footprint "eagle-import:WIRELESS-BLUETOOTH-HC-05")
      (libsource (lib "eagle-import") (part "WIRELESS-BLUETOOTH-HC-05"))
    )
    (comp (ref "U2")
      (value "SX1509")
      (footprint "eagle-import:QFN-28")
      (libsource (lib "eagle-import") (part "SX1509"))
    )
    (comp (ref "WS2812")
      (value "PINHD-1X3")
      (footprint "eagle-import:1X03")
      (libsource (lib "eagle-import") (part "PINHD-1X3"))
    )
    (comp (ref "IC1")
      (value "L293D")
      (footprint "eagle-import:L293")
      (libsource (lib "eagle-import") (part "L293D"))
    )
    (comp (ref "JP2")
      (value "ServoA")
      (footprint "eagle-import:1X03")
      (libsource (lib "eagle-import") (part "PINHD-1X3"))
    )
    (comp (ref "JP3")
      (value "ServoB")
      (footprint "eagle-import:1X03")
      (libsource (lib "eagle-import") (part "PINHD-1X3"))
    )
    (comp (ref "JP4")
      (value "ServoC")
      (footprint "eagle-import:1X03")
      (libsource (lib "eagle-import") (part "PINHD-1X3"))
    )
    (comp (ref "R12")
      (value "10k")
      (footprint "eagle-import:R1206")
      (libsource (lib "eagle-import") (part "R-EU_R1206"))
    )
    (comp (ref "R13")
      (value "10k")
      (footprint "eagle-import:R1206")
      (libsource (lib "eagle-import") (part "R-EU_R1206"))
    )
    (comp (ref "R14")
      (value "10k")
      (footprint "eagle-import:R1206")
      (libsource (lib "eagle-import") (part "R-EU_R1206"))
    )
    (comp (ref "R15")
      (value "10k")
      (footprint "eagle-import:R1206")
      (libsource (lib "eagle-import") (part "R-EU_R1206"))
    )
    (comp (ref "SW6")
      (value "USB_SWITCH")
      (footprint "eagle-import:USB_SWITCH")
      (libsource (lib "eagle-import") (part "USB_SWITCH"))
    )
    (comp (ref "JP5")
      (value "ICSP")
      (footprint "eagle-import:ICSP_HEADER")
      (libsource (lib "eagle-import") (part "ICSP_HEADER"))
    )
    (comp (ref "JP23")
      (value "PINHD-1X2")
      (footprint "eagle-import:1X02")
      (libsource (lib "eagle-import") (part "PINHD-1X2"))
    )
    (comp (ref "MOT_A")
      (value "MKDSN1,5/2-5,08")
      (footprint "eagle-import:MKDSN1,5_2-5,08")
      (libsource (lib "eagle-import") (part "MKDSN1,5/2-5,08"))
    )
    (comp (ref "MOT_B")
      (value "MKDSN1,5/2-5,08")
      (footprint "eagle-import:MKDSN1,5_2-5,08")
      (libsource (lib "eagle-import") (part "MKDSN1,5/2-5,08"))
    )
    (comp (ref "Q2")
      (value "BSS138")
      (footprint "eagle-import:SOT23")
      (fields (field (name "MF") "Fairchild"))
      (libsource (lib "eagle-import") (part "BSS138"))
    )
    (comp (ref "Q3")
      (value "BSS138")
      (footprint "eagle-import:SOT23")
      (fields (field (name "MF") "Fairchild"))
      (libsource (lib "eagle-import") (part "BSS138"))
    )
    (comp (ref "Q4")
      (value "BSS138")
      (footprint "eagle-import:SOT23")
      (fields (field (name "MF") "Fairchild"))
      (libsource (lib "eagle-import") (part "BSS138"))
    )
    (comp (ref "Q5")
      (value "BSS138")
      (footprint "eagle-import:SOT23")
      (fields (field (name "MF") "Fairchild"))
      (libsource (lib "eagle-import") (part "BSS138"))
    )
    (comp (ref "R33")
      (value "10k")
      (footprint "eagle-import:R1206")
      (libsource (lib "eagle-import") (part "R-EU_R1206"))
    )
    (comp (ref "R34")
      (value "10k")
      (footprint "eagle-import:R1206")
      (libsource (lib "eagle-import") (part "R-EU_R1206"))
    )
    (comp (ref "R35")
      (value "10k")
      (footprint "eagle-import:R1206")
      (libsource (lib "eagle-import") (part "R-EU_R1206"))
    )
    (comp (ref "R36")
      (value "100")
      (footprint "eagle-import:R1206")
      (libsource (lib "eagle-import") (part "R-EU_R1206"))
    )
    (comp (ref "R37")
      (value "10k")
      (footprint "eagle-import:R1206")
      (libsource (lib "eagle-import") (part "R-EU_R1206"))
    )
    (comp (ref "R38")
      (value "10k")
      (footprint "eagle-import:R1206")
      (libsource (lib "eagle-import") (part "R-EU_R1206"))
    )
    (comp (ref "R39")
      (value "10k")
      (footprint "eagle-import:R1206")
      (libsource (lib "eagle-import") (part "R-EU_R1206"))
    )
    (comp (ref "R40")
      (value "10k")
      (footprint "eagle-import:R1206")
      (libsource (lib "eagle-import") (part "R-EU_R1206"))
    )
    (comp (ref "R44")
      (value "100R")
      (footprint "eagle-import:R1206")
      (libsource (lib "eagle-import") (part "R-EU_R1206"))
    )
    (comp (ref "SW4")
      (value "USB_SWITCH")
      (footprint "eagle-import:USB_SWITCH")
      (libsource (lib "eagle-import") (part "USB_SWITCH"))
    )
    (comp (ref "U$2")
      (value "Header 2")
      (footprint "eagle-import:BIG_HEADER")
      (libsource (lib "eagle-import") (part "BIG_HEADER"))
    )
    (comp (ref "U$3")
      (value "I2C_HEADER")
      (footprint "eagle-import:I2_HEADER")
      (libsource (lib "eagle-import") (part "I2C_HEADER"))
    )
    (comp (ref "U$4")
      (value "SERIAL_HEADER")
      (footprint "eagle-import:SERIAL_HEADER")
      (libsource (lib "eagle-import") (part "SERIAL_HEADER"))
    )
    (comp (ref "U$9")
      (value "POLULU_MOTOR")
      (footprint "eagle-import:POLULU_MOTOR")
      (libsource (lib "eagle-import") (part "POLULU_MOTOR"))
    )
    (comp (ref "U$16")
      (value "BAT+")
      (footprint "eagle-import:LEGO-1X1")
      (libsource (lib "eagle-import") (part "LEGO-1X1"))
    )
    (comp (ref "U$17")
      (value "3.3V")
      (footprint "eagle-import:LEGO-1X1")
      (libsource (lib "eagle-import") (part "LEGO-1X1"))
    )
    (comp (ref "U$18")
      (value "GND")
      (footprint "eagle-import:LEGO-1X1")
      (libsource (lib "eagle-import") (part "LEGO-1X1"))
    )
    (comp (ref "U$19")
      (value "GND")
      (footprint "eagle-import:LEGO-1X1")
      (libsource (lib "eagle-import") (part "LEGO-1X1"))
    )
    (comp (ref "U$20")
      (value "BALL")
      (footprint "eagle-import:BALL")
      (libsource (lib "eagle-import") (part "BALL"))
    )
    (comp (ref "U$22")
      (value "OPENSOURCE")
      (footprint "eagle-import:OSHW_5MM")
      (libsource (lib "eagle-import") (part "OPENSOURCE"))
    )
    (comp (ref "U$24")
      (value "POLULU_MOTOR")
      (footprint "eagle-import:POLULU_MOTOR")
      (libsource (lib "eagle-import") (part "POLULU_MOTOR"))
    )
    (comp (ref "VERSION")
      (value "4.1")
      (footprint "eagle-import:VERSION")
      (libsource (lib "eagle-import") (part "VERSION"))
    )
  )
  (nets
    (net (code "1") (name "+3V3") (class "Default")
      (node (ref "C10") (pin "1") (pinfunction "1_1") (pintype "passive"))
      (node (ref "C11") (pin "2") (pinfunction "2_2") (pintype "passive"))
      (node (ref "C12") (pin "1") (pinfunction "1_1") (pintype "passive"))
      (node (ref "C13") (pin "1") (pinfunction "1_1") (pintype "passive"))
      (node (ref "C19") (pin "1") (pinfunction "1_1") (pintype "passive"))
      (node (ref "C20") (pin "1") (pinfunction "1_1") (pintype "passive"))
      (node (ref "C21") (pin "2") (pinfunction "2_2") (pintype "passive"))
      (node (ref "C22") (pin "1") (pinfunction "1_1") (pintype "passive"))
      (node (ref "C26") (pin "2") (pinfunction "2_2") (pintype "passive"))
      (node (ref "C28") (pin "1") (pinfunction "1_1") (pintype "passive"))
      (node (ref "C29") (pin "2") (pinfunction "2_2") (pintype "passive"))
      (node (ref "C30") (pin "2") (pinfunction "2_2") (pintype "passive"))
      (node (ref "C31") (pin "2") (pinfunction "2_2") (pintype "passive"))
      (node (ref "C5") (pin "1") (pinfunction "1_1") (pintype "passive"))
      (node (ref "C6") (pin "2") (pinfunction "2_2") (pintype "passive"))
      (node (ref "IC1") (pin "16") (pinfunction "VCC1_16") (pintype "power_in"))
      (node (ref "IC4") (pin "2") (pinfunction "CSB_2") (pintype "input"))
      (node (ref "IC4") (pin "5") (pinfunction "SDO_5") (pintype "input"))
      (node (ref "IC4") (pin "6") (pinfunction "VDDIO_6") (pintype "power_in"))
      (node (ref "IC4") (pin "8") (pinfunction "VDD_8") (pintype "power_in"))
      (node (ref "IC5") (pin "2") (pinfunction "CSB_2") (pintype "input"))
      (node (ref "IC5") (pin "6") (pinfunction "VDDIO_6") (pintype "power_in"))
      (node (ref "IC5") (pin "8") (pinfunction "VDD_8") (pintype "power_in"))
      (node (ref "JP21") (pin "1") (pinfunction "1_1") (pintype "passive"))
      (node (ref "JP22") (pin "1") (pinfunction "1_1") (pintype "passive"))
      (node (ref "POT") (pin "E") (pinfunction "E_E") (pintype "passive"))
      (node (ref "Q2") (pin "1") (pinfunction "G_1") (pintype "passive"))
      (node (ref "Q3") (pin "1") (pinfunction "G_1") (pintype "passive"))
      (node (ref "Q4") (pin "1") (pinfunction "G_1") (pintype "passive"))
      (node (ref "Q5") (pin "1") (pinfunction "G_1") (pintype "passive"))
      (node (ref "R1") (pin "2") (pinfunction "2_2") (pintype "passive"))
      (node (ref "R10") (pin "2") (pinfunction "2_2") (pintype "passive"))
      (node (ref "R13") (pin "2") (pinfunction "2_2") (pintype "passive"))
      (node (ref "R14") (pin "1") (pinfunction "1_1") (pintype "passive"))
      (node (ref "R16") (pin "1") (pinfunction "1_1") (pintype "passive"))
      (node (ref "R17") (pin "1") (pinfunction "1_1") (pintype "passive"))
      (node (ref "R18") (pin "1") (pinfunction "1_1") (pintype "passive"))
      (node (ref "R19") (pin "1") (pinfunction "1_1") (pintype "passive"))
      (node (ref "R20") (pin "2") (pinfunction "2_2") (pintype "passive"))
      (node (ref "R29") (pin "2") (pinfunction "2_2") (pintype "passive"))
      (node (ref "R30") (pin "2") (pinfunction "2_2") (pintype "passive"))
      (node (ref "R31") (pin "2") (pinfunction "2_2") (pintype "passive"))
      (node (ref "R32") (pin "2") (pinfunction "2_2") (pintype "passive"))
      (node (ref "R34") (pin "1") (pinfunction "1_1") (pintype "passive"))
      (node (ref "R38") (pin "1") (pinfunction "1_1") (pintype "passive"))
      (node (ref "R40") (pin "1") (pinfunction "1_1") (pintype "passive"))
      (node (ref "R42") (pin "1") (pinfunction "1_1") (pintype "passive"))
      (node (ref "R43") (pin "2") (pinfunction "2_2") (pintype "passive"))
      (node (ref "S4") (pin "2") (pinfunction "S1_2") (pintype "passive"))
      (node (ref "TSOP4838") (pin "VCC") (pinfunction "V+_VCC") (pintype "bidirectional"))
      (node (ref "U$1") (pin "VCC") (pinfunction "VCC_VCC") (pintype "bidirectional"))
      (node (ref "U$1") (pin "VCC2") (pinfunction "VCC2_VCC2") (pintype "bidirectional"))
      (node (ref "U$1") (pin "VCC3") (pinfunction "VCC3_VCC3") (pintype "bidirectional"))
      (node (ref "U$12") (pin "+5V") (pinfunction "+5V_+5V") (pintype "bidirectional"))
      (node (ref "U$15") (pin "1") (pinfunction "VCC_1") (pintype "power_in"))
      (node (ref "U$17") (pin "LEGO") (pinfunction "LEGO_LEGO") (pintype "bidirectional"))
      (node (ref "U$2") (pin "+3V3") (pinfunction "+3V3_+3V3") (pintype "passive"))
      (node (ref "U$25") (pin "3") (pinfunction "VO_3") (pintype "passive"))
      (node (ref "U$26") (pin "3") (pinfunction "VO_3") (pintype "passive"))
      (node (ref "U$3") (pin "+5V") (pinfunction "+5V_+5V") (pintype "bidirectional"))
      (node (ref "U$3") (pin "5V") (pinfunction "5V_5V") (pintype "bidirectional"))
      (node (ref "U$4") (pin "+5V") (pinfunction "+5V_+5V") (pintype "bidirectional"))
      (node (ref "U$4") (pin "5V") (pinfunction "5V_5V") (pintype "bidirectional"))
      (node (ref "U2") (pin "12") (pinfunction "VDDM_12") (pintype "bidirectional"))
      (node (ref "U2") (pin "18") (pinfunction "VCC2_18") (pintype "bidirectional"))
      (node (ref "U2") (pin "4") (pinfunction "VCC1_4") (pintype "bidirectional"))
      (node (ref "U3") (pin "VCC") (pinfunction "VCC_VCC") (pintype "bidirectional"))
      (node (ref "U4") (pin "5") (pinfunction "VCC_5") (pintype "power_in"))
      (node (ref "U4") (pin "8") (pinfunction "V3_8") (pintype "input"))
    )
    (net (code "2") (name "+5V") (class "Default")
      (node (ref "JP5") (pin "2") (pinfunction "2_2") (pintype "passive"))
      (node (ref "R33") (pin "1") (pinfunction "1_1") (pintype "passive"))
      (node (ref "R35") (pin "1") (pinfunction "1_1") (pintype "passive"))
      (node (ref "R36") (pin "1") (pinfunction "1_1") (pintype "passive"))
      (node (ref "R37") (pin "1") (pinfunction "1_1") (pintype "passive"))
      (node (ref "R39") (pin "1") (pinfunction "1_1") (pintype "passive"))
      (node (ref "R44") (pin "1") (pinfunction "1_1") (pintype "passive"))
    )
    (net (code "3") (name "36") (class "Default")
      (node (ref "U$1") (pin "36") (pinfunction "36_36") (pintype "bidirectional"))
      (node (ref "U$2") (pin "+5V1") (pinfunction "+5V1_+5V1") (pintype "passive"))
    )
    (net (code "4") (name "A0") (class "Default")
      (node (ref "SW7") (pin "COM1") (pinfunction "COM1_COM1") (pintype "bidirectional"))
      (node (ref "U$1") (pin "A0") (pinfunction "A0_A0") (pintype "bidirectional"))
    )
    (net (code "5") (name "A0H") (class "Default")
      (node (ref "SW7") (pin "CH1B") (pinfunction "CH1B_CH1B") (pintype "bidirectional"))
      (node (ref "U$2") (pin "A0") (pinfunction "A0_A0") (pintype "passive"))
    )
    (net (code "6") (name "A1") (class "Default")
      (node (ref "POT") (pin "S") (pinfunction "S_S") (pintype "passive"))
      (node (ref "U$1") (pin "A1") (pinfunction "A1_A1") (pintype "bidirectional"))
      (node (ref "U$2") (pin "A1") (pinfunction "A1_A1") (pintype "passive"))
    )
    (net (code "7") (name "A2") (class "Default")
      (node (ref "R27") (pin "1") (pinfunction "1_1") (pintype "passive"))
      (node (ref "U$1") (pin "A2") (pinfunction "A2_A2") (pintype "bidirectional"))
    )
    (net (code "8") (name "A3") (class "Default")
      (node (ref "R28") (pin "2") (pinfunction "2_2") (pintype "passive"))
      (node (ref "U$1") (pin "A3") (pinfunction "A3_A3") (pintype "bidirectional"))
    )
    (net (code "9") (name "A6") (class "Default")
      (node (ref "SW4") (pin "COM1") (pinfunction "COM1_COM1") (pintype "bidirectional"))
      (node (ref "U$1") (pin "A6") (pinfunction "A6_A6") (pintype "bidirectional"))
    )
    (net (code "10") (name "A7") (class "Default")
      (node (ref "R21") (pin "2") (pinfunction "P$2_2") (pintype "bidirectional"))
      (node (ref "R32") (pin "1") (pinfunction "1_1") (pintype "passive"))
      (node (ref "U$1") (pin "A7") (pinfunction "A7_A7") (pintype "bidirectional"))
      (node (ref "U$2") (pin "A7") (pinfunction "A7_A7") (pintype "passive"))
    )
    (net (code "11") (name "ATMEGA_D+") (class "Default")
      (node (ref "SW1") (pin "CH2A") (pinfunction "CH2A_CH2A") (pintype "bidirectional"))
      (node (ref "U$1") (pin "D+") (pinfunction "D+_D+") (pintype "bidirectional"))
    )
    (net (code "12") (name "ATMEGA_D-") (class "Default")
      (node (ref "SW1") (pin "CH1A") (pinfunction "CH1A_CH1A") (pintype "bidirectional"))
      (node (ref "U$1") (pin "D-") (pinfunction "D-_D-") (pintype "bidirectional"))
    )
    (net (code "13") (name "BAT+") (class "Default")
      (node (ref "C15") (pin "1") (pinfunction "1_1") (pintype "passive"))
      (node (ref "L1") (pin "1") (pinfunction "1_1") (pintype "passive"))
      (node (ref "R41") (pin "1") (pinfunction "1_1") (pintype "passive"))
      (node (ref "R48") (pin "2") (pinfunction "2_2") (pintype "passive"))
      (node (ref "U$13") (pin "4") (pinfunction "AIN0_4") (pintype "input"))
      (node (ref "U$13") (pin "7") (pinfunction "AIN3_7") (pintype "input"))
      (node (ref "U$16") (pin "LEGO") (pinfunction "LEGO_LEGO") (pintype "bidirectional"))
      (node (ref "U$2") (pin "+5V") (pinfunction "+5V_+5V") (pintype "passive"))
      (node (ref "U$25") (pin "1") (pinfunction "VI_1") (pintype "input"))
      (node (ref "U$26") (pin "1") (pinfunction "VI_1") (pintype "input"))
      (node (ref "U$5") (pin "P$4") (pinfunction "EN_P$4") (pintype "bidirectional"))
      (node (ref "U$5") (pin "P$5") (pinfunction "IN_P$5") (pintype "bidirectional"))
    )
    (net (code "14") (name "BAT-") (class "Default")
      (node (ref "1") (pin "2") (pinfunction "S_2") (pintype "passive"))
      (node (ref "1") (pin "3") (pinfunction "S_3") (pintype "passive"))
      (node (ref "8205") (pin "2") (pinfunction "S_2") (pintype "passive"))
      (node (ref "8205") (pin "3") (pinfunction "S_3") (pintype "passive"))
      (node (ref "BT1") (pin "GND@1") (pinfunction "-_GND@1") (pintype "power_in"))
      (node (ref "C16") (pin "2") (pinfunction "2_2") (pintype "passive"))
      (node (ref "C27") (pin "-") (pinfunction "-_-") (pintype "passive"))
      (node (ref "ON") (pin "C") (pinfunction "C_C") (pintype "passive"))
      (node (ref "Q6") (pin "1") (pinfunction "G_1") (pintype "passive"))
      (node (ref "Q7") (pin "1") (pinfunction "G_1") (pintype "passive"))
      (node (ref "R6") (pin "1") (pinfunction "1_1") (pintype "passive"))
      (node (ref "T1") (pin "2") (pinfunction "S_2") (pintype "passive"))
      (node (ref "T1") (pin "3") (pinfunction "S_3") (pintype "passive"))
      (node (ref "T2") (pin "2") (pinfunction "S_2") (pintype "passive"))
      (node (ref "T2") (pin "3") (pinfunction "S_3") (pintype "passive"))
      (node (ref "U$7") (pin "-") (pinfunction "-_-") (pintype "power_in"))
      (node (ref "U$8") (pin "6") (pinfunction "GND_6") (pintype "bidirectional"))
    )
    (net (code "15") (name "BUTTON") (class "Default")
      (node (ref "C26") (pin "1") (pinfunction "1_1") (pintype "passive"))
      (node (ref "R2") (pin "2") (pinfunction "2_2") (pintype "passive"))
      (node (ref "S4") (pin "4") (pinfunction "P1_4") (pintype "passive"))
      (node (ref "SW4") (pin "CH1B") (pinfunction "CH1B_CH1B") (pintype "bidirectional"))
    )
    (net (code "16") (name "CUR-SENSE") (class "Default")
      (node (ref "R22") (pin "1") (pinfunction "1_1") (pintype "passive"))
      (node (ref "R41") (pin "2") (pinfunction "2_2") (pintype "passive"))
      (node (ref "SW5") (pin "CH1B") (pinfunction "CH1B_CH1B") (pintype "bidirectional"))
      (node (ref "SW5") (pin "CH2B") (pinfunction "CH2B_CH2B") (pintype "bidirectional"))
      (node (ref "U$13") (pin "6") (pinfunction "AIN2_6") (pintype "input"))
    )
    (net (code "17") (name "D+") (class "Default")
      (node (ref "IC3") (pin "15") (pinfunction "USBDP_15") (pintype "bidirectional"))
      (node (ref "SW1") (pin "CH2B") (pinfunction "CH2B_CH2B") (pintype "bidirectional"))
      (node (ref "U4") (pin "1") (pinfunction "USB_D+_1") (pintype "bidirectional"))
    )
    (net (code "18") (name "D-") (class "Default")
      (node (ref "IC3") (pin "16") (pinfunction "USBDM_16") (pintype "bidirectional"))
      (node (ref "SW1") (pin "CH1B") (pinfunction "CH1B_CH1B") (pintype "bidirectional"))
      (node (ref "U4") (pin "2") (pinfunction "USB_D-_2") (pintype "input"))
    )
    (net (code "19") (name "D2") (class "Default")
      (node (ref "U$1") (pin "D2") (pinfunction "D2_D2") (pintype "bidirectional"))
      (node (ref "U$2") (pin "D2") (pinfunction "D2_D2") (pintype "passive"))
      (node (ref "U$23") (pin "3") (pinfunction "TX_3") (pintype "bidirectional"))
    )
    (net (code "20") (name "D3") (class "Default")
      (node (ref "U$1") (pin "D3") (pinfunction "D3_D3") (pintype "bidirectional"))
      (node (ref "U$2") (pin "D3") (pinfunction "D3_D3") (pintype "passive"))
    )
    (net (code "21") (name "D4") (class "Default")
      (node (ref "TSOP4838") (pin "OUT") (pinfunction "OUT_OUT") (pintype "bidirectional"))
      (node (ref "U$1") (pin "D4") (pinfunction "D4_D4") (pintype "bidirectional"))
      (node (ref "U$2") (pin "D4") (pinfunction "D4_D4") (pintype "passive"))
    )
    (net (code "22") (name "D5") (class "Default")
      (node (ref "U$1") (pin "D5") (pinfunction "D5_D5") (pintype "bidirectional"))
      (node (ref "U$2") (pin "D5") (pinfunction "D5_D5") (pintype "passive"))
      (node (ref "U$23") (pin "2") (pinfunction "RX_2") (pintype "bidirectional"))
    )
    (net (code "23") (name "D6") (class "Default")
      (node (ref "JP4") (pin "1") (pinfunction "1_1") (pintype "passive"))
      (node (ref "U$1") (pin "D6") (pinfunction "D6_D6") (pintype "bidirectional"))
      (node (ref "U$2") (pin "D6") (pinfunction "D6_D6") (pintype "passive"))
    )
    (net (code "24") (name "GND") (class "Default")
      (node (ref "1") (pin "6") (pinfunction "S_6") (pintype "passive"))
      (node (ref "1") (pin "7") (pinfunction "S_7") (pintype "passive"))
      (node (ref "8205") (pin "6") (pinfunction "S_6") (pintype "passive"))
      (node (ref "8205") (pin "7") (pinfunction "S_7") (pintype "passive"))
      (node (ref "C1") (pin "2") (pinfunction "2_2") (pintype "passive"))
      (node (ref "C10") (pin "2") (pinfunction "2_2") (pintype "passive"))
      (node (ref "C11") (pin "1") (pinfunction "1_1") (pintype "passive"))
      (node (ref "C12") (pin "2") (pinfunction "2_2") (pintype "passive"))
      (node (ref "C13") (pin "2") (pinfunction "2_2") (pintype "passive"))
      (node (ref "C14") (pin "2") (pinfunction "2_2") (pintype "passive"))
      (node (ref "C15") (pin "2") (pinfunction "2_2") (pintype "passive"))
      (node (ref "C17") (pin "-") (pinfunction "-_-") (pintype "passive"))
      (node (ref "C19") (pin "2") (pinfunction "2_2") (pintype "passive"))
      (node (ref "C2") (pin "2") (pinfunction "2_2") (pintype "passive"))
      (node (ref "C20") (pin "2") (pinfunction "2_2") (pintype "passive"))
      (node (ref "C21") (pin "1") (pinfunction "1_1") (pintype "passive"))
      (node (ref "C22") (pin "2") (pinfunction "2_2") (pintype "passive"))
      (node (ref "C23") (pin "-") (pinfunction "-_-") (pintype "passive"))
      (node (ref "C24") (pin "2") (pinfunction "2_2") (pintype "passive"))
      (node (ref "C25") (pin "1") (pinfunction "1_1") (pintype "passive"))
      (node (ref "C28") (pin "2") (pinfunction "2_2") (pintype "passive"))
      (node (ref "C29") (pin "1") (pinfunction "1_1") (pintype "passive"))
      (node (ref "C30") (pin "1") (pinfunction "1_1") (pintype "passive"))
      (node (ref "C31") (pin "1") (pinfunction "1_1") (pintype "passive"))
      (node (ref "C4") (pin "2") (pinfunction "2_2") (pintype "passive"))
      (node (ref "C5") (pin "2") (pinfunction "2_2") (pintype "passive"))
      (node (ref "C6") (pin "1") (pinfunction "1_1") (pintype "passive"))
      (node (ref "C7") (pin "1") (pinfunction "1_1") (pintype "passive"))
      (node (ref "C8") (pin "1") (pinfunction "1_1") (pintype "passive"))
      (node (ref "C9") (pin "2") (pinfunction "2_2") (pintype "passive"))
      (node (ref "D1") (pin "A") (pinfunction "A_A") (pintype "passive"))
      (node (ref "IC1") (pin "12") (pinfunction "GND4_12") (pintype "power_in"))
      (node (ref "IC1") (pin "13") (pinfunction "GND3_13") (pintype "power_in"))
      (node (ref "IC1") (pin "4") (pinfunction "GND1_4") (pintype "power_in"))
      (node (ref "IC1") (pin "5") (pinfunction "GND2_5") (pintype "power_in"))
      (node (ref "IC2") (pin "3") (pinfunction "GND_3") (pintype "power_in"))
      (node (ref "IC3") (pin "18") (pinfunction "GND_18") (pintype "power_in"))
      (node (ref "IC3") (pin "21") (pinfunction "GND_21") (pintype "power_in"))
      (node (ref "IC3") (pin "25") (pinfunction "AGND_25") (pintype "power_in"))
      (node (ref "IC3") (pin "26") (pinfunction "TEST_26") (pintype "bidirectional"))
      (node (ref "IC3") (pin "7") (pinfunction "GND_7") (pintype "power_in"))
      (node (ref "IC4") (pin "1") (pinfunction "GND_1") (pintype "power_in"))
      (node (ref "IC4") (pin "7") (pinfunction "GND_7") (pintype "power_in"))
      (node (ref "IC5") (pin "1") (pinfunction "GND_1") (pintype "power_in"))
      (node (ref "IC5") (pin "5") (pinfunction "SDO_5") (pintype "input"))
      (node (ref "IC5") (pin "7") (pinfunction "GND_7") (pintype "power_in"))
      (node (ref "JP2") (pin "3") (pinfunction "3_3") (pintype "passive"))
      (node (ref "JP3") (pin "3") (pinfunction "3_3") (pintype "passive"))
      (node (ref "JP4") (pin "3") (pinfunction "3_3") (pintype "passive"))
      (node (ref "JP5") (pin "6") (pinfunction "6_6") (pintype "passive"))
      (node (ref "LED10") (pin "4") (pinfunction "GND_4") (pintype "power_in"))
      (node (ref "LED11") (pin "4") (pinfunction "GND_4") (pintype "power_in"))
      (node (ref "LED4") (pin "4") (pinfunction "GND_4") (pintype "power_in"))
      (node (ref "LED5") (pin "3") (pinfunction "VSS_3") (pintype "bidirectional"))
      (node (ref "LED6") (pin "3") (pinfunction "VSS_3") (pintype "bidirectional"))
      (node (ref "LED7") (pin "3") (pinfunction "VSS_3") (pintype "bidirectional"))
      (node (ref "LED8") (pin "3") (pinfunction "VSS_3") (pintype "bidirectional"))
      (node (ref "LED9") (pin "4") (pinfunction "GND_4") (pintype "power_in"))
      (node (ref "LS1") (pin "E") (pinfunction "EMITTER_E") (pintype "passive"))
      (node (ref "LS1") (pin "K") (pinfunction "CATHODE_K") (pintype "passive"))
      (node (ref "LS2") (pin "E") (pinfunction "EMITTER_E") (pintype "passive"))
      (node (ref "LS2") (pin "K") (pinfunction "CATHODE_K") (pintype "passive"))
      (node (ref "POT") (pin "A") (pinfunction "A_A") (pintype "passive"))
      (node (ref "R12") (pin "2") (pinfunction "2_2") (pintype "passive"))
      (node (ref "R15") (pin "1") (pinfunction "1_1") (pintype "passive"))
      (node (ref "R2") (pin "1") (pinfunction "1_1") (pintype "passive"))
      (node (ref "R21") (pin "1") (pinfunction "P$1_1") (pintype "bidirectional"))
      (node (ref "R23") (pin "1") (pinfunction "P$1_1") (pintype "bidirectional"))
      (node (ref "R46") (pin "2") (pinfunction "2_2") (pintype "passive"))
      (node (ref "R47") (pin "2") (pinfunction "2_2") (pintype "passive"))
      (node (ref "R8") (pin "2") (pinfunction "2_2") (pintype "passive"))
      (node (ref "S2") (pin "4") (pinfunction "P1_4") (pintype "passive"))
      (node (ref "T1") (pin "6") (pinfunction "S_6") (pintype "passive"))
      (node (ref "T1") (pin "7") (pinfunction "S_7") (pintype "passive"))
      (node (ref "T2") (pin "6") (pinfunction "S_6") (pintype "passive"))
      (node (ref "T2") (pin "7") (pinfunction "S_7") (pintype "passive"))
      (node (ref "TP4056") (pin "1") (pinfunction "TEMP_1") (pintype "bidirectional"))
      (node (ref "TP4056") (pin "3") (pinfunction "GND_3") (pintype "bidirectional"))
      (node (ref "TSOP4838") (pin "GND") (pinfunction "GND_GND") (pintype "bidirectional"))
      (node (ref "U$1") (pin "GND") (pinfunction "GND_GND") (pintype "bidirectional"))
      (node (ref "U$1") (pin "GND2") (pinfunction "GND2_GND2") (pintype "bidirectional"))
      (node (ref "U$1") (pin "GND3") (pinfunction "GND3_GND3") (pintype "bidirectional"))
      (node (ref "U$12") (pin "GND") (pinfunction "GND_GND") (pintype "bidirectional"))
      (node (ref "U$13") (pin "1") (pinfunction "ADDR_1") (pintype "input"))
      (node (ref "U$13") (pin "3") (pinfunction "GND_3") (pintype "power_in"))
      (node (ref "U$13") (pin "5") (pinfunction "AIN1_5") (pintype "input"))
      (node (ref "U$14") (pin "2") (pinfunction "GND_2") (pintype "power_in"))
      (node (ref "U$15") (pin "2") (pinfunction "GND_2") (pintype "power_in"))
      (node (ref "U$18") (pin "LEGO") (pinfunction "LEGO_LEGO") (pintype "bidirectional"))
      (node (ref "U$19") (pin "LEGO") (pinfunction "LEGO_LEGO") (pintype "bidirectional"))
      (node (ref "U$2") (pin "GND") (pinfunction "GND_GND") (pintype "passive"))
      (node (ref "U$2") (pin "GND2") (pinfunction "GND1_GND2") (pintype "passive"))
      (node (ref "U$23") (pin "4") (pinfunction "GND_4") (pintype "power_in"))
      (node (ref "U$25") (pin "2") (pinfunction "GND_2") (pintype "passive"))
      (node (ref "U$25") (pin "TAB") (pinfunction "GND_2_TAB") (pintype "passive"))
      (node (ref "U$26") (pin "2") (pinfunction "GND_2") (pintype "passive"))
      (node (ref "U$26") (pin "TAB") (pinfunction "GND_2_TAB") (pintype "passive"))
      (node (ref "U$3") (pin "GND1") (pinfunction "GND_GND1") (pintype "bidirectional"))
      (node (ref "U$3") (pin "GND2") (pinfunction "GND2_GND2") (pintype "bidirectional"))
      (node (ref "U$4") (pin "GND") (pinfunction "GND_GND") (pintype "bidirectional"))
      (node (ref "U$4") (pin "GND2") (pinfunction "GND2_GND2") (pintype "bidirectional"))
      (node (ref "U$5") (pin "P$2") (pinfunction "GND_P$2") (pintype "bidirectional"))
      (node (ref "U$6") (pin "-") (pinfunction "-_-") (pintype "power_in"))
      (node (ref "U1") (pin "GND1") (pinfunction "GND_GND1") (pintype "bidirectional"))
      (node (ref "U1") (pin "ID1") (pinfunction "USBID_ID1") (pintype "bidirectional"))
      (node (ref "U2") (pin "10") (pinfunction "ADDR1_10") (pintype "bidirectional"))
      (node (ref "U2") (pin "17") (pinfunction "GND_17") (pintype "bidirectional"))
      (node (ref "U2") (pin "26") (pinfunction "ADDR0_26") (pintype "bidirectional"))
      (node (ref "U2") (pin "29") (pinfunction "GND_29") (pintype "bidirectional"))
      (node (ref "U2") (pin "3") (pinfunction "GND_3") (pintype "bidirectional"))
      (node (ref "U3") (pin "GND") (pinfunction "GND_GND") (pintype "bidirectional"))
      (node (ref "U4") (pin "3") (pinfunction "GND_3") (pintype "power_in"))
      (node (ref "WS2812") (pin "3") (pinfunction "3_3") (pintype "passive"))
    )
    (net (code "25") (name "HD_A6") (class "Default")
      (node (ref "SW4") (pin "CH1A") (pinfunction "CH1A_CH1A") (pintype "bidirectional"))
      (node (ref "U$2") (pin "A6") (pinfunction "A6_A6") (pintype "passive"))
    )
    (net (code "26") (name "IN_A1") (class "Default")
      (node (ref "IC1") (pin "2") (pinfunction "1A_2") (pintype "input"))
      (node (ref "JP3") (pin "1") (pinfunction "1_1") (pintype "passive"))
      (node (ref "R14") (pin "2") (pinfunction "2_2") (pintype "passive"))
      (node (ref "U$1") (pin "D10") (pinfunction "D10_D10") (pintype "bidirectional"))
    )
    (net (code "27") (name "IN_A2") (class "Default")
      (node (ref "IC1") (pin "7") (pinfunction "2A_7") (pintype "input"))
      (node (ref "JP2") (pin "1") (pinfunction "1_1") (pintype "passive"))
      (node (ref "R15") (pin "2") (pinfunction "2_2") (pintype "passive"))
      (node (ref "U$1") (pin "D9") (pinfunction "D9_D9") (pintype "bidirectional"))
    )
    (net (code "28") (name "IN_B1") (class "Default")
      (node (ref "IC1") (pin "15") (pinfunction "4A_15") (pintype "input"))
      (node (ref "R13") (pin "1") (pinfunction "1_1") (pintype "passive"))
      (node (ref "U$1") (pin "D8") (pinfunction "D8_D8") (pintype "bidirectional"))
    )
    (net (code "29") (name "IN_B2") (class "Default")
      (node (ref "IC1") (pin "10") (pinfunction "3A_10") (pintype "input"))
      (node (ref "R12") (pin "1") (pinfunction "1_1") (pintype "passive"))
      (node (ref "U$1") (pin "D7") (pinfunction "D7_D7") (pintype "bidirectional"))
    )
    (net (code "30") (name "IRFU") (class "Default")
      (node (ref "BT1") (pin "PWR@1") (pinfunction "+_PWR@1") (pintype "power_in"))
      (node (ref "C1") (pin "1") (pinfunction "1_1") (pintype "passive"))
      (node (ref "Q6") (pin "3") (pinfunction "D_3") (pintype "passive"))
      (node (ref "Q7") (pin "3") (pinfunction "D_3") (pintype "passive"))
      (node (ref "REV") (pin "C") (pinfunction "C_C") (pintype "passive"))
      (node (ref "SJ2") (pin "1") (pinfunction "1_1") (pintype "passive"))
      (node (ref "U$7") (pin "+") (pinfunction "+_+") (pintype "power_in"))
    )
    (net (code "31") (name "MISO") (class "Default")
      (node (ref "IC1") (pin "1") (pinfunction "1-2EN_1") (pintype "input"))
      (node (ref "Q4") (pin "2") (pinfunction "S_2") (pintype "passive"))
      (node (ref "R38") (pin "2") (pinfunction "2_2") (pintype "passive"))
      (node (ref "U$1") (pin "D12") (pinfunction "D12_D12") (pintype "bidirectional"))
    )
    (net (code "32") (name "MISO_HV") (class "Default")
      (node (ref "JP5") (pin "1") (pinfunction "1_1") (pintype "passive"))
      (node (ref "Q4") (pin "3") (pinfunction "D_3") (pintype "passive"))
      (node (ref "R37") (pin "2") (pinfunction "2_2") (pintype "passive"))
    )
    (net (code "33") (name "MOSI") (class "Default")
      (node (ref "IC1") (pin "9") (pinfunction "3-4EN_9") (pintype "input"))
      (node (ref "Q2") (pin "2") (pinfunction "S_2") (pintype "passive"))
      (node (ref "R34") (pin "2") (pinfunction "2_2") (pintype "passive"))
      (node (ref "U$1") (pin "D11") (pinfunction "D11_D11") (pintype "bidirectional"))
    )
    (net (code "34") (name "MOSI_HV") (class "Default")
      (node (ref "JP5") (pin "4") (pinfunction "4_4") (pintype "passive"))
      (node (ref "Q2") (pin "3") (pinfunction "D_3") (pintype "passive"))
      (node (ref "R33") (pin "2") (pinfunction "2_2") (pintype "passive"))
    )
    (net (code "35") (name "MOT_A+") (class "Default")
      (node (ref "IC1") (pin "3") (pinfunction "1Y_3") (pintype "output"))
      (node (ref "MOT_A") (pin "2") (pinfunction "KL_2") (pintype "passive"))
      (node (ref "U$24") (pin "+") (pinfunction "+_+") (pintype "bidirectional"))
    )
    (net (code "36") (name "MOT_A-") (class "Default")
      (node (ref "IC1") (pin "6") (pinfunction "2Y_6") (pintype "output"))
      (node (ref "MOT_A") (pin "1") (pinfunction "KL_1") (pintype "passive"))
      (node (ref "U$24") (pin "-") (pinfunction "-_-") (pintype "bidirectional"))
    )
    (net (code "37") (name "MOT_B+") (class "Default")
      (node (ref "IC1") (pin "14") (pinfunction "4Y_14") (pintype "output"))
      (node (ref "MOT_B") (pin "2") (pinfunction "KL_2") (pintype "passive"))
      (node (ref "U$9") (pin "+") (pinfunction "+_+") (pintype "bidirectional"))
    )
    (net (code "38") (name "MOT_B-") (class "Default")
      (node (ref "IC1") (pin "11") (pinfunction "3Y_11") (pintype "output"))
      (node (ref "MOT_B") (pin "1") (pinfunction "KL_1") (pintype "passive"))
      (node (ref "U$9") (pin "-") (pinfunction "-_-") (pintype "bidirectional"))
    )
    (net (code "39") (name "Net-(1A-D)") (class "Default")
      (node (ref "1") (pin "1") (pinfunction "D_1") (pintype "passive"))
      (node (ref "1") (pin "8") (pinfunction "D_8") (pintype "passive"))
    )
    (net (code "40") (name "Net-(1A-G)") (class "Default")
      (node (ref "1") (pin "4") (pinfunction "G_4") (pintype "passive"))
      (node (ref "8205") (pin "4") (pinfunction "G_4") (pintype "passive"))
      (node (ref "T1") (pin "4") (pinfunction "G_4") (pintype "passive"))
      (node (ref "T2") (pin "4") (pinfunction "G_4") (pintype "passive"))
      (node (ref "U$8") (pin "1") (pinfunction "0D_1") (pintype "bidirectional"))
    )
    (net (code "41") (name "Net-(1B-G)") (class "Default")
      (node (ref "1") (pin "5") (pinfunction "G_5") (pintype "passive"))
      (node (ref "8205") (pin "5") (pinfunction "G_5") (pintype "passive"))
      (node (ref "T1") (pin "5") (pinfunction "G_5") (pintype "passive"))
      (node (ref "T2") (pin "5") (pinfunction "G_5") (pintype "passive"))
      (node (ref "U$8") (pin "3") (pinfunction "0C_3") (pintype "bidirectional"))
    )
    (net (code "42") (name "Net-(8205A-D)") (class "Default")
      (node (ref "8205") (pin "1") (pinfunction "D_1") (pintype "passive"))
      (node (ref "8205") (pin "8") (pinfunction "D_8") (pintype "passive"))
    )
    (net (code "43") (name "Net-(C7-Pad2)") (class "Default")
      (node (ref "C7") (pin "2") (pinfunction "2_2") (pintype "passive"))
      (node (ref "Q1") (pin "1") (pinfunction "1_1") (pintype "passive"))
      (node (ref "U$1") (pin "CRYST1") (pinfunction "CRYST1_CRYST1") (pintype "bidirectional"))
    )
    (net (code "44") (name "Net-(C8-Pad2)") (class "Default")
      (node (ref "C8") (pin "2") (pinfunction "2_2") (pintype "passive"))
      (node (ref "Q1") (pin "3") (pinfunction "3_3") (pintype "passive"))
      (node (ref "U$1") (pin "CRYST2") (pinfunction "CRYST2_CRYST2") (pintype "bidirectional"))
    )
    (net (code "45") (name "Net-(C14-Pad1)") (class "Default")
      (node (ref "C14") (pin "1") (pinfunction "1_1") (pintype "passive"))
      (node (ref "D3") (pin "C") (pinfunction "C_C") (pintype "passive"))
      (node (ref "R49") (pin "1") (pinfunction "1_1") (pintype "passive"))
      (node (ref "R9") (pin "1") (pinfunction "1_1") (pintype "passive"))
      (node (ref "SJ1") (pin "1") (pinfunction "1_1") (pintype "passive"))
    )
    (net (code "46") (name "Net-(IC1-VCC2)") (class "Default")
      (node (ref "IC1") (pin "8") (pinfunction "VCC2_8") (pintype "power_in"))
      (node (ref "SW6") (pin "CH1A") (pinfunction "CH1A_CH1A") (pintype "bidirectional"))
      (node (ref "SW6") (pin "CH2A") (pinfunction "CH2A_CH2A") (pintype "bidirectional"))
    )
    (net (code "47") (name "Net-(IC2-OUT)") (class "Default")
      (node (ref "D1") (pin "C") (pinfunction "C_C") (pintype "passive"))
      (node (ref "IC2") (pin "2") (pinfunction "OUT_2") (pintype "output"))
      (node (ref "L2") (pin "1") (pinfunction "1_1") (pintype "passive"))
    )
    (net (code "48") (name "Net-(IC3-3V3OUT)") (class "Default")
      (node (ref "C2") (pin "1") (pinfunction "1_1") (pintype "passive"))
      (node (ref "IC3") (pin "17") (pinfunction "3V3OUT_17") (pintype "output"))
      (node (ref "IC3") (pin "4") (pinfunction "VCCIO_4") (pintype "power_in"))
      (node (ref "R24") (pin "1") (pinfunction "1_1") (pintype "passive"))
      (node (ref "R25") (pin "1") (pinfunction "1_1") (pintype "passive"))
    )
    (net (code "49") (name "Net-(IC3-CBUS0)") (class "Default")
      (node (ref "IC3") (pin "23") (pinfunction "CBUS0_23") (pintype "bidirectional"))
      (node (ref "TXD") (pin "C") (pinfunction "C_C") (pintype "passive"))
    )
    (net (code "50") (name "Net-(IC3-CBUS1)") (class "Default")
      (node (ref "IC3") (pin "22") (pinfunction "CBUS1_22") (pintype "bidirectional"))
      (node (ref "LED3") (pin "C") (pinfunction "C_C") (pintype "passive"))
    )
    (net (code "51") (name "Net-(IC3-_DTR)") (class "Default")
      (node (ref "C3") (pin "1") (pinfunction "1_1") (pintype "passive"))
      (node (ref "IC3") (pin "2") (pinfunction "_DTR_2") (pintype "input"))
    )
    (net (code "52") (name "Net-(IC3-_RTS)") (class "Default")
      (node (ref "C18") (pin "2") (pinfunction "2_2") (pintype "passive"))
      (node (ref "IC3") (pin "3") (pinfunction "_RTS_3") (pintype "output"))
    )
    (net (code "53") (name "Net-(LED1-PadC)") (class "Default")
      (node (ref "LED1") (pin "C") (pinfunction "C_C") (pintype "passive"))
      (node (ref "R5") (pin "1") (pinfunction "1_1") (pintype "passive"))
    )
    (net (code "54") (name "Net-(LED3-PadA)") (class "Default")
      (node (ref "LED3") (pin "A") (pinfunction "A_A") (pintype "passive"))
      (node (ref "R24") (pin "2") (pinfunction "2_2") (pintype "passive"))
    )
    (net (code "55") (name "Net-(LED4-DI)") (class "Default")
      (node (ref "LED4") (pin "1") (pinfunction "DI_1") (pintype "input"))
      (node (ref "LED6") (pin "2") (pinfunction "DO_2") (pintype "bidirectional"))
      (node (ref "LED7") (pin "4") (pinfunction "DI_4") (pintype "bidirectional"))
      (node (ref "LED9") (pin "3") (pinfunction "DO_3") (pintype "output"))
    )
    (net (code "56") (name "Net-(LED10-DI)") (class "Default")
      (node (ref "LED10") (pin "1") (pinfunction "DI_1") (pintype "input"))
      (node (ref "LED5") (pin "4") (pinfunction "DI_4") (pintype "bidirectional"))
      (node (ref "R7") (pin "1") (pinfunction "1_1") (pintype "passive"))
    )
    (net (code "57") (name "Net-(LED10-DO)") (class "Default")
      (node (ref "LED10") (pin "3") (pinfunction "DO_3") (pintype "output"))
      (node (ref "LED5") (pin "2") (pinfunction "DO_2") (pintype "bidirectional"))
      (node (ref "LED6") (pin "4") (pinfunction "DI_4") (pintype "bidirectional"))
      (node (ref "LED9") (pin "1") (pinfunction "DI_1") (pintype "input"))
    )
    (net (code "58") (name "Net-(LED11-DI)") (class "Default")
      (node (ref "LED11") (pin "1") (pinfunction "DI_1") (pintype "input"))
      (node (ref "LED4") (pin "3") (pinfunction "DO_3") (pintype "output"))
      (node (ref "LED7") (pin "2") (pinfunction "DO_2") (pintype "bidirectional"))
      (node (ref "LED8") (pin "4") (pinfunction "DI_4") (pintype "bidirectional"))
    )
    (net (code "59") (name "Net-(LED11-DO)") (class "Default")
      (node (ref "LED11") (pin "3") (pinfunction "DO_3") (pintype "output"))
      (node (ref "LED8") (pin "2") (pinfunction "DO_2") (pintype "bidirectional"))
      (node (ref "WS2812") (pin "2") (pinfunction "2_2") (pintype "passive"))
    )
    (net (code "60") (name "Net-(LS1-ANODE)") (class "Default")
      (node (ref "LS1") (pin "A") (pinfunction "ANODE_A") (pintype "passive"))
      (node (ref "R18") (pin "2") (pinfunction "2_2") (pintype "passive"))
    )
    (net (code "61") (name "Net-(LS1-COLLECTOR)") (class "Default")
      (node (ref "LS1") (pin "C") (pinfunction "COLLECTOR_C") (pintype "passive"))
      (node (ref "R19") (pin "2") (pinfunction "2_2") (pintype "passive"))
      (node (ref "SW3") (pin "CH1B") (pinfunction "CH1B_CH1B") (pintype "bidirectional"))
      (node (ref "TXD1") (pin "C") (pinfunction "C_C") (pintype "passive"))
    )
    (net (code "62") (name "Net-(LS2-ANODE)") (class "Default")
      (node (ref "LS2") (pin "A") (pinfunction "ANODE_A") (pintype "passive"))
      (node (ref "R16") (pin "2") (pinfunction "2_2") (pintype "passive"))
    )
    (net (code "63") (name "Net-(LS2-COLLECTOR)") (class "Default")
      (node (ref "LS2") (pin "C") (pinfunction "COLLECTOR_C") (pintype "passive"))
      (node (ref "R17") (pin "2") (pinfunction "2_2") (pintype "passive"))
      (node (ref "SW2") (pin "CH1A") (pinfunction "CH1A_CH1A") (pintype "bidirectional"))
      (node (ref "TXD2") (pin "C") (pinfunction "C_C") (pintype "passive"))
    )
    (net (code "64") (name "Net-(ON-PadA)") (class "Default")
      (node (ref "ON") (pin "A") (pinfunction "A_A") (pintype "passive"))
      (node (ref "R22") (pin "2") (pinfunction "2_2") (pintype "passive"))
    )
    (net (code "65") (name "Net-(Q6-S)") (class "Default")
      (node (ref "C27") (pin "+") (pinfunction "+_+") (pintype "passive"))
      (node (ref "Q6") (pin "2") (pinfunction "S_2") (pintype "passive"))
      (node (ref "Q7") (pin "2") (pinfunction "S_2") (pintype "passive"))
      (node (ref "SJ2") (pin "2") (pinfunction "2_2") (pintype "passive"))
      (node (ref "SW5") (pin "COM1") (pinfunction "COM1_COM1") (pintype "bidirectional"))
      (node (ref "SW5") (pin "COM2") (pinfunction "COM2_COM2") (pintype "bidirectional"))
      (node (ref "TP4056") (pin "5") (pinfunction "BAT_5") (pintype "bidirectional"))
    )
    (net (code "66") (name "Net-(R4-Pad2)") (class "Default")
      (node (ref "R4") (pin "2") (pinfunction "2_2") (pintype "passive"))
      (node (ref "R8") (pin "1") (pinfunction "1_1") (pintype "passive"))
    )
    (net (code "67") (name "Net-(R6-Pad2)") (class "Default")
      (node (ref "R6") (pin "2") (pinfunction "2_2") (pintype "passive"))
      (node (ref "REV") (pin "A") (pinfunction "A_A") (pintype "passive"))
    )
    (net (code "68") (name "Net-(R10-Pad1)") (class "Default")
      (node (ref "R10") (pin "1") (pinfunction "1_1") (pintype "passive"))
      (node (ref "TXD1") (pin "A") (pinfunction "A_A") (pintype "passive"))
    )
    (net (code "69") (name "Net-(R11-Pad1)") (class "Default")
      (node (ref "R11") (pin "1") (pinfunction "1_1") (pintype "passive"))
      (node (ref "YELLOW") (pin "C") (pinfunction "C_C") (pintype "passive"))
    )
    (net (code "70") (name "Net-(R20-Pad1)") (class "Default")
      (node (ref "R20") (pin "1") (pinfunction "1_1") (pintype "passive"))
      (node (ref "TXD2") (pin "A") (pinfunction "A_A") (pintype "passive"))
    )
    (net (code "71") (name "Net-(R23-P$2)") (class "Default")
      (node (ref "R23") (pin "2") (pinfunction "P$2_2") (pintype "bidirectional"))
      (node (ref "R29") (pin "1") (pinfunction "1_1") (pintype "passive"))
      (node (ref "SW7") (pin "CH1A") (pinfunction "CH1A_CH1A") (pintype "bidirectional"))
    )
    (net (code "72") (name "Net-(R25-Pad2)") (class "Default")
      (node (ref "R25") (pin "2") (pinfunction "2_2") (pintype "passive"))
      (node (ref "TXD") (pin "A") (pinfunction "A_A") (pintype "passive"))
    )
    (net (code "73") (name "Net-(R26-Pad2)") (class "Default")
      (node (ref "R26") (pin "2") (pinfunction "2_2") (pintype "passive"))
      (node (ref "U$12") (pin "A1") (pinfunction "A1_A1") (pintype "bidirectional"))
    )
    (net (code "74") (name "Net-(R27-Pad2)") (class "Default")
      (node (ref "R27") (pin "2") (pinfunction "2_2") (pintype "passive"))
      (node (ref "SW3") (pin "COM1") (pinfunction "COM1_COM1") (pintype "bidirectional"))
    )
    (net (code "75") (name "Net-(R28-Pad1)") (class "Default")
      (node (ref "R28") (pin "1") (pinfunction "1_1") (pintype "passive"))
      (node (ref "SW2") (pin "COM1") (pinfunction "COM1_COM1") (pintype "bidirectional"))
    )
    (net (code "76") (name "Net-(SW2-PadCH1B)") (class "Default")
      (node (ref "SW2") (pin "CH1B") (pinfunction "CH1B_CH1B") (pintype "bidirectional"))
      (node (ref "U$12") (pin "A3") (pinfunction "A3_A3") (pintype "bidirectional"))
    )
    (net (code "77") (name "Net-(SW3-PadCH1A)") (class "Default")
      (node (ref "SW3") (pin "CH1A") (pinfunction "CH1A_CH1A") (pintype "bidirectional"))
      (node (ref "U$12") (pin "A2") (pinfunction "A2_A2") (pintype "bidirectional"))
    )
    (net (code "78") (name "Net-(T1A-D)") (class "Default")
      (node (ref "T1") (pin "1") (pinfunction "D_1") (pintype "passive"))
      (node (ref "T1") (pin "8") (pinfunction "D_8") (pintype "passive"))
    )
    (net (code "79") (name "Net-(T2A-D)") (class "Default")
      (node (ref "T2") (pin "1") (pinfunction "D_1") (pintype "passive"))
      (node (ref "T2") (pin "8") (pinfunction "D_8") (pintype "passive"))
    )
    (net (code "80") (name "Net-(TP4056-CE)") (class "Default")
      (node (ref "LED1") (pin "A") (pinfunction "A_A") (pintype "passive"))
      (node (ref "R3") (pin "2") (pinfunction "2_2") (pintype "passive"))
      (node (ref "TP4056") (pin "4") (pinfunction "VCC_4") (pintype "bidirectional"))
      (node (ref "TP4056") (pin "8") (pinfunction "CE_8") (pintype "bidirectional"))
      (node (ref "YELLOW") (pin "A") (pinfunction "A_A") (pintype "passive"))
    )
    (net (code "81") (name "Net-(TP4056-CHRG)") (class "Default")
      (node (ref "R5") (pin "2") (pinfunction "2_2") (pintype "passive"))
      (node (ref "TP4056") (pin "7") (pinfunction "CHRG_7") (pintype "bidirectional"))
    )
    (net (code "82") (name "Net-(TP4056-PROG)") (class "Default")
      (node (ref "R4") (pin "1") (pinfunction "1_1") (pintype "passive"))
      (node (ref "TP4056") (pin "2") (pinfunction "PROG_2") (pintype "bidirectional"))
    )
    (net (code "83") (name "Net-(TP4056-STDBY)") (class "Default")
      (node (ref "R11") (pin "2") (pinfunction "2_2") (pintype "passive"))
      (node (ref "TP4056") (pin "6") (pinfunction "STDBY_6") (pintype "bidirectional"))
    )
    (net (code "84") (name "Net-(U$5-FB)") (class "Default")
      (node (ref "R46") (pin "1") (pinfunction "1_1") (pintype "passive"))
      (node (ref "R49") (pin "2") (pinfunction "2_2") (pintype "passive"))
      (node (ref "R9") (pin "2") (pinfunction "2_2") (pintype "passive"))
      (node (ref "U$5") (pin "P$3") (pinfunction "FB_P$3") (pintype "bidirectional"))
    )
    (net (code "85") (name "Net-(U$5-SW)") (class "Default")
      (node (ref "D3") (pin "A") (pinfunction "A_A") (pintype "passive"))
      (node (ref "L1") (pin "2") (pinfunction "2_2") (pintype "passive"))
      (node (ref "U$5") (pin "P$1") (pinfunction "SW_P$1") (pintype "bidirectional"))
    )
    (net (code "86") (name "Net-(U$8-CS)") (class "Default")
      (node (ref "R47") (pin "1") (pinfunction "1_1") (pintype "passive"))
      (node (ref "U$8") (pin "2") (pinfunction "CS_2") (pintype "bidirectional"))
    )
    (net (code "87") (name "Net-(U$8-VCC)") (class "Default")
      (node (ref "C16") (pin "1") (pinfunction "1_1") (pintype "passive"))
      (node (ref "R48") (pin "1") (pinfunction "1_1") (pintype "passive"))
      (node (ref "U$8") (pin "5") (pinfunction "VCC_5") (pintype "bidirectional"))
    )
    (net (code "88") (name "Net-(U1-D+)") (class "Default")
      (node (ref "SW1") (pin "COM2") (pinfunction "COM2_COM2") (pintype "bidirectional"))
      (node (ref "U1") (pin "D+1") (pinfunction "D+_D+1") (pintype "bidirectional"))
    )
    (net (code "89") (name "Net-(U1-D-)") (class "Default")
      (node (ref "SW1") (pin "COM1") (pinfunction "COM1_COM1") (pintype "bidirectional"))
      (node (ref "U1") (pin "D-1") (pinfunction "D-_D-1") (pintype "bidirectional"))
    )
    (net (code "90") (name "Net-(U2-I{slash}O[0])") (class "Default")
      (node (ref "JP11") (pin "1") (pinfunction "1_1") (pintype "passive"))
      (node (ref "U2") (pin "27") (pinfunction "I/O[0]_27") (pintype "bidirectional"))
    )
    (net (code "91") (name "Net-(U2-I{slash}O[1])") (class "Default")
      (node (ref "JP10") (pin "1") (pinfunction "1_1") (pintype "passive"))
      (node (ref "U2") (pin "28") (pinfunction "I/O[1]_28") (pintype "bidirectional"))
    )
    (net (code "92") (name "Net-(U2-I{slash}O[2])") (class "Default")
      (node (ref "JP8") (pin "1") (pinfunction "1_1") (pintype "passive"))
      (node (ref "U2") (pin "1") (pinfunction "I/O[2]_1") (pintype "bidirectional"))
    )
    (net (code "93") (name "Net-(U2-I{slash}O[3])") (class "Default")
      (node (ref "JP9") (pin "1") (pinfunction "1_1") (pintype "passive"))
      (node (ref "U2") (pin "2") (pinfunction "I/O[3]_2") (pintype "bidirectional"))
    )
    (net (code "94") (name "Net-(U2-I{slash}O[4])") (class "Default")
      (node (ref "JP7") (pin "1") (pinfunction "1_1") (pintype "passive"))
      (node (ref "U2") (pin "5") (pinfunction "I/O[4]_5") (pintype "bidirectional"))
    )
    (net (code "95") (name "Net-(U2-I{slash}O[5])") (class "Default")
      (node (ref "JP6") (pin "1") (pinfunction "1_1") (pintype "passive"))
      (node (ref "U2") (pin "6") (pinfunction "I/O[5]_6") (pintype "bidirectional"))
    )
    (net (code "96") (name "Net-(U2-I{slash}O[6])") (class "Default")
      (node (ref "JP1") (pin "1") (pinfunction "1_1") (pintype "passive"))
      (node (ref "U2") (pin "7") (pinfunction "I/O[6]_7") (pintype "bidirectional"))
    )
    (net (code "97") (name "Net-(U2-I{slash}O[7])") (class "Default")
      (node (ref "JP18") (pin "1") (pinfunction "1_1") (pintype "passive"))
      (node (ref "U2") (pin "8") (pinfunction "I/O[7]_8") (pintype "bidirectional"))
    )
    (net (code "98") (name "Net-(U2-I{slash}O[8])") (class "Default")
      (node (ref "JP17") (pin "1") (pinfunction "1_1") (pintype "passive"))
      (node (ref "U2") (pin "13") (pinfunction "I/O[8]_13") (pintype "bidirectional"))
    )
    (net (code "99") (name "Net-(U2-I{slash}O[9])") (class "Default")
      (node (ref "JP16") (pin "1") (pinfunction "1_1") (pintype "passive"))
      (node (ref "U2") (pin "14") (pinfunction "I/O[9]_14") (pintype "bidirectional"))
    )
    (net (code "100") (name "Net-(U2-I{slash}O[10])") (class "Default")
      (node (ref "JP15") (pin "1") (pinfunction "1_1") (pintype "passive"))
      (node (ref "U2") (pin "15") (pinfunction "I/O[10]_15") (pintype "bidirectional"))
    )
    (net (code "101") (name "Net-(U2-I{slash}O[11])") (class "Default")
      (node (ref "JP19") (pin "1") (pinfunction "1_1") (pintype "passive"))
      (node (ref "U2") (pin "16") (pinfunction "I/O[11]_16") (pintype "bidirectional"))
    )
    (net (code "102") (name "Net-(U2-I{slash}O[12])") (class "Default")
      (node (ref "JP14") (pin "1") (pinfunction "1_1") (pintype "passive"))
      (node (ref "U2") (pin "19") (pinfunction "I/O[12]_19") (pintype "bidirectional"))
    )
    (net (code "103") (name "Net-(U2-I{slash}O[13])") (class "Default")
      (node (ref "JP13") (pin "1") (pinfunction "1_1") (pintype "passive"))
      (node (ref "U2") (pin "20") (pinfunction "I/O[13]_20") (pintype "bidirectional"))
    )
    (net (code "104") (name "Net-(U2-I{slash}O[14])") (class "Default")
      (node (ref "JP12") (pin "1") (pinfunction "1_1") (pintype "passive"))
      (node (ref "U2") (pin "21") (pinfunction "I/O[14]_21") (pintype "bidirectional"))
    )
    (net (code "105") (name "Net-(U2-I{slash}O[15])") (class "Default")
      (node (ref "JP20") (pin "1") (pinfunction "1_1") (pintype "passive"))
      (node (ref "U2") (pin "22") (pinfunction "I/O[15]_22") (pintype "bidirectional"))
    )
    (net (code "106") (name "Net-(U2-~{INT})") (class "Default")
      (node (ref "R42") (pin "2") (pinfunction "2_2") (pintype "passive"))
      (node (ref "U2") (pin "9") (pinfunction "~{INT}_9") (pintype "bidirectional"))
    )
    (net (code "107") (name "Net-(U2-~{RESET})") (class "Default")
      (node (ref "R43") (pin "1") (pinfunction "1_1") (pintype "passive"))
      (node (ref "U2") (pin "23") (pinfunction "~{RESET}_23") (pintype "bidirectional"))
    )
    (net (code "108") (name "RESET") (class "Default")
      (node (ref "C18") (pin "1") (pinfunction "1_1") (pintype "passive"))
      (node (ref "C25") (pin "2") (pinfunction "2_2") (pintype "passive"))
      (node (ref "C3") (pin "2") (pinfunction "2_2") (pintype "passive"))
      (node (ref "Q3") (pin "2") (pinfunction "S_2") (pintype "passive"))
      (node (ref "R1") (pin "1") (pinfunction "1_1") (pintype "passive"))
      (node (ref "S2") (pin "2") (pinfunction "S1_2") (pintype "passive"))
      (node (ref "U$1") (pin "RESET") (pinfunction "RESET_RESET") (pintype "bidirectional"))
    )
    (net (code "109") (name "RESET_HV") (class "Default")
      (node (ref "JP5") (pin "5") (pinfunction "5_5") (pintype "passive"))
      (node (ref "Q3") (pin "3") (pinfunction "D_3") (pintype "passive"))
      (node (ref "R35") (pin "2") (pinfunction "2_2") (pintype "passive"))
    )
    (net (code "110") (name "RXD") (class "Default")
      (node (ref "IC3") (pin "1") (pinfunction "TXD_1") (pintype "output"))
      (node (ref "U$1") (pin "D0") (pinfunction "D0_D0") (pintype "bidirectional"))
      (node (ref "U$2") (pin "D0") (pinfunction "D0_D0") (pintype "passive"))
      (node (ref "U$4") (pin "RXD") (pinfunction "RXD1_RXD") (pintype "bidirectional"))
      (node (ref "U$4") (pin "RXD2") (pinfunction "RXD2_RXD2") (pintype "bidirectional"))
      (node (ref "U4") (pin "6") (pinfunction "TXD_6") (pintype "output"))
    )
    (net (code "111") (name "SCK") (class "Default")
      (node (ref "Q5") (pin "2") (pinfunction "S_2") (pintype "passive"))
      (node (ref "R26") (pin "1") (pinfunction "1_1") (pintype "passive"))
      (node (ref "R40") (pin "2") (pinfunction "2_2") (pintype "passive"))
      (node (ref "R7") (pin "2") (pinfunction "2_2") (pintype "passive"))
      (node (ref "U$1") (pin "D13") (pinfunction "D13_D13") (pintype "bidirectional"))
    )
    (net (code "112") (name "SCK_HV") (class "Default")
      (node (ref "JP5") (pin "3") (pinfunction "3_3") (pintype "passive"))
      (node (ref "Q5") (pin "3") (pinfunction "D_3") (pintype "passive"))
      (node (ref "R39") (pin "2") (pinfunction "2_2") (pintype "passive"))
    )
    (net (code "113") (name "SCL") (class "Default")
      (node (ref "IC4") (pin "4") (pinfunction "SCK_4") (pintype "bidirectional"))
      (node (ref "IC5") (pin "4") (pinfunction "SCK_4") (pintype "bidirectional"))
      (node (ref "JP23") (pin "2") (pinfunction "2_2") (pintype "passive"))
      (node (ref "R30") (pin "1") (pinfunction "1_1") (pintype "passive"))
      (node (ref "U$1") (pin "A5") (pinfunction "A5_A5") (pintype "bidirectional"))
      (node (ref "U$13") (pin "10") (pinfunction "SCL_10") (pintype "bidirectional"))
      (node (ref "U$14") (pin "3") (pinfunction "SCL_3") (pintype "bidirectional"))
      (node (ref "U$15") (pin "3") (pinfunction "SCL_3") (pintype "bidirectional"))
      (node (ref "U$2") (pin "A5") (pinfunction "A5_A5") (pintype "passive"))
      (node (ref "U$3") (pin "SCL") (pinfunction "SCL_SCL") (pintype "bidirectional"))
      (node (ref "U$3") (pin "SCL2") (pinfunction "SCL2_SCL2") (pintype "bidirectional"))
      (node (ref "U2") (pin "25") (pinfunction "SCL_25") (pintype "bidirectional"))
      (node (ref "U3") (pin "SCL") (pinfunction "SCL_SCL") (pintype "bidirectional"))
    )
    (net (code "114") (name "SDA") (class "Default")
      (node (ref "IC4") (pin "3") (pinfunction "SDI_3") (pintype "bidirectional"))
      (node (ref "IC5") (pin "3") (pinfunction "SDI_3") (pintype "bidirectional"))
      (node (ref "JP23") (pin "1") (pinfunction "1_1") (pintype "passive"))
      (node (ref "R31") (pin "1") (pinfunction "1_1") (pintype "passive"))
      (node (ref "U$1") (pin "A4") (pinfunction "A4_A4") (pintype "bidirectional"))
      (node (ref "U$13") (pin "9") (pinfunction "SDA_9") (pintype "bidirectional"))
      (node (ref "U$14") (pin "4") (pinfunction "SDA_4") (pintype "bidirectional"))
      (node (ref "U$15") (pin "4") (pinfunction "SDA_4") (pintype "bidirectional"))
      (node (ref "U$2") (pin "A4") (pinfunction "A4_A4") (pintype "passive"))
      (node (ref "U$3") (pin "SDA") (pinfunction "SDA_SDA") (pintype "bidirectional"))
      (node (ref "U$3") (pin "SDA2") (pinfunction "SDA2_SDA2") (pintype "bidirectional"))
      (node (ref "U2") (pin "24") (pinfunction "SDA_24") (pintype "bidirectional"))
      (node (ref "U3") (pin "SDA") (pinfunction "SDA_SDA") (pintype "bidirectional"))
    )
    (net (code "115") (name "TXD") (class "Default")
      (node (ref "IC3") (pin "5") (pinfunction "RXD_5") (pintype "input"))
      (node (ref "U$1") (pin "D1") (pinfunction "D1_D1") (pintype "bidirectional"))
      (node (ref "U$2") (pin "D1") (pinfunction "D1_D1") (pintype "passive"))
      (node (ref "U$4") (pin "TXD") (pinfunction "TXD_TXD") (pintype "bidirectional"))
      (node (ref "U$4") (pin "TXD2") (pinfunction "TXD2_TXD2") (pintype "bidirectional"))
      (node (ref "U4") (pin "7") (pinfunction "RXD_7") (pintype "input"))
    )
    (net (code "116") (name "VCC_MOT") (class "Default")
      (node (ref "C23") (pin "+") (pinfunction "+_+") (pintype "passive"))
      (node (ref "C24") (pin "1") (pinfunction "1_1") (pintype "passive"))
      (node (ref "IC2") (pin "1") (pinfunction "VIN_1") (pintype "power_in"))
      (node (ref "SJ1") (pin "2") (pinfunction "2_2") (pintype "passive"))
      (node (ref "SW6") (pin "COM1") (pinfunction "COM1_COM1") (pintype "bidirectional"))
      (node (ref "SW6") (pin "COM2") (pinfunction "COM2_COM2") (pintype "bidirectional"))
      (node (ref "U$6") (pin "+") (pinfunction "+_+") (pintype "power_in"))
    )
    (net (code "117") (name "VCC_SERVO") (class "Default")
      (node (ref "C17") (pin "+") (pinfunction "+_+") (pintype "passive"))
      (node (ref "C4") (pin "1") (pinfunction "1_1") (pintype "passive"))
      (node (ref "C9") (pin "1") (pinfunction "1_1") (pintype "passive"))
      (node (ref "IC2") (pin "4") (pinfunction "FB_4") (pintype "input"))
      (node (ref "JP2") (pin "2") (pinfunction "2_2") (pintype "passive"))
      (node (ref "JP3") (pin "2") (pinfunction "2_2") (pintype "passive"))
      (node (ref "JP4") (pin "2") (pinfunction "2_2") (pintype "passive"))
      (node (ref "L2") (pin "2") (pinfunction "2_2") (pintype "passive"))
      (node (ref "LED10") (pin "2") (pinfunction "VDD_2") (pintype "power_in"))
      (node (ref "LED11") (pin "2") (pinfunction "VDD_2") (pintype "power_in"))
      (node (ref "LED4") (pin "2") (pinfunction "VDD_2") (pintype "power_in"))
      (node (ref "LED5") (pin "1") (pinfunction "VDD_1") (pintype "bidirectional"))
      (node (ref "LED6") (pin "1") (pinfunction "VDD_1") (pintype "bidirectional"))
      (node (ref "LED7") (pin "1") (pinfunction "VDD_1") (pintype "bidirectional"))
      (node (ref "LED8") (pin "1") (pinfunction "VDD_1") (pintype "bidirectional"))
      (node (ref "LED9") (pin "2") (pinfunction "VDD_2") (pintype "power_in"))
      (node (ref "R36") (pin "2") (pinfunction "2_2") (pintype "passive"))
      (node (ref "R44") (pin "2") (pinfunction "2_2") (pintype "passive"))
      (node (ref "U$13") (pin "8") (pinfunction "VDD_8") (pintype "power_in"))
      (node (ref "U$14") (pin "1") (pinfunction "VIN_1") (pintype "power_in"))
      (node (ref "U$23") (pin "5") (pinfunction "+5V_5") (pintype "power_in"))
      (node (ref "WS2812") (pin "1") (pinfunction "1_1") (pintype "passive"))
    )
    (net (code "118") (name "VUSB") (class "Default")
      (node (ref "IC3") (pin "20") (pinfunction "VCC_20") (pintype "power_in"))
      (node (ref "R3") (pin "1") (pinfunction "1_1") (pintype "passive"))
      (node (ref "U1") (pin "VBUS1") (pinfunction "VBUS_VBUS1") (pintype "bidirectional"))
    )
    (net (code "119") (name "unconnected-(IC2-OFF-Pad5)") (class "Default")
      (node (ref "IC2") (pin "5") (pinfunction "OFF_5") (pintype "input"))
    )
    (net (code "120") (name "unconnected-(IC3-CBUS2-Pad13)") (class "Default")
      (node (ref "IC3") (pin "13") (pinfunction "CBUS2_13") (pintype "bidirectional"))
    )
    (net (code "121") (name "unconnected-(IC3-CBUS3-Pad14)") (class "Default")
      (node (ref "IC3") (pin "14") (pinfunction "CBUS3_14") (pintype "bidirectional"))
    )
    (net (code "122") (name "unconnected-(IC3-CBUS4-Pad12)") (class "Default")
      (node (ref "IC3") (pin "12") (pinfunction "CBUS4_12") (pintype "bidirectional"))
    )
    (net (code "123") (name "unconnected-(IC3-NC-Pad8)") (class "Default")
      (node (ref "IC3") (pin "8") (pinfunction "NC_8") (pintype "no_connect"))
    )
    (net (code "124") (name "unconnected-(IC3-NC-Pad24)") (class "Default")
      (node (ref "IC3") (pin "24") (pinfunction "NC_24") (pintype "no_connect"))
    )
    (net (code "125") (name "unconnected-(IC3-OSCI-Pad27)") (class "Default")
      (node (ref "IC3") (pin "27") (pinfunction "OSCI_27") (pintype "input"))
    )
    (net (code "126") (name "unconnected-(IC3-OSCO-Pad28)") (class "Default")
      (node (ref "IC3") (pin "28") (pinfunction "OSCO_28") (pintype "output"))
    )
    (net (code "127") (name "unconnected-(IC3-_CTS-Pad11)") (class "Default")
      (node (ref "IC3") (pin "11") (pinfunction "_CTS_11") (pintype "input"))
    )
    (net (code "128") (name "unconnected-(IC3-_DCD-Pad10)") (class "Default")
      (node (ref "IC3") (pin "10") (pinfunction "_DCD_10") (pintype "input"))
    )
    (net (code "129") (name "unconnected-(IC3-_DSR-Pad9)") (class "Default")
      (node (ref "IC3") (pin "9") (pinfunction "_DSR_9") (pintype "input"))
    )
    (net (code "130") (name "unconnected-(IC3-_RESET-Pad19)") (class "Default")
      (node (ref "IC3") (pin "19") (pinfunction "_RESET_19") (pintype "input"))
    )
    (net (code "131") (name "unconnected-(IC3-_RI-Pad6)") (class "Default")
      (node (ref "IC3") (pin "6") (pinfunction "_RI_6") (pintype "input"))
    )
    (net (code "132") (name "unconnected-(Q1-Pad2)") (class "Default")
      (node (ref "Q1") (pin "2") (pinfunction "2_2") (pintype "passive"))
    )
    (net (code "133") (name "unconnected-(S2-P-Pad3)") (class "Default")
      (node (ref "S2") (pin "3") (pinfunction "P_3") (pintype "passive"))
    )
    (net (code "134") (name "unconnected-(S2-S-Pad1)") (class "Default")
      (node (ref "S2") (pin "1") (pinfunction "S_1") (pintype "passive"))
    )
    (net (code "135") (name "unconnected-(S4-P-Pad3)") (class "Default")
      (node (ref "S4") (pin "3") (pinfunction "P_3") (pintype "passive"))
    )
    (net (code "136") (name "unconnected-(S4-S-Pad1)") (class "Default")
      (node (ref "S4") (pin "1") (pinfunction "S_1") (pintype "passive"))
    )
    (net (code "137") (name "unconnected-(SW2-PadCH2A)") (class "Default")
      (node (ref "SW2") (pin "CH2A") (pinfunction "CH2A_CH2A") (pintype "bidirectional"))
    )
    (net (code "138") (name "unconnected-(SW2-PadCH2B)") (class "Default")
      (node (ref "SW2") (pin "CH2B") (pinfunction "CH2B_CH2B") (pintype "bidirectional"))
    )
    (net (code "139") (name "unconnected-(SW2-PadCOM2)") (class "Default")
      (node (ref "SW2") (pin "COM2") (pinfunction "COM2_COM2") (pintype "bidirectional"))
    )
    (net (code "140") (name "unconnected-(SW3-PadCH2A)") (class "Default")
      (node (ref "SW3") (pin "CH2A") (pinfunction "CH2A_CH2A") (pintype "bidirectional"))
    )
    (net (code "141") (name "unconnected-(SW3-PadCH2B)") (class "Default")
      (node (ref "SW3") (pin "CH2B") (pinfunction "CH2B_CH2B") (pintype "bidirectional"))
    )
    (net (code "142") (name "unconnected-(SW3-PadCOM2)") (class "Default")
      (node (ref "SW3") (pin "COM2") (pinfunction "COM2_COM2") (pintype "bidirectional"))
    )
    (net (code "143") (name "unconnected-(SW4-PadCH2A)") (class "Default")
      (node (ref "SW4") (pin "CH2A") (pinfunction "CH2A_CH2A") (pintype "bidirectional"))
    )
    (net (code "144") (name "unconnected-(SW4-PadCH2B)") (class "Default")
      (node (ref "SW4") (pin "CH2B") (pinfunction "CH2B_CH2B") (pintype "bidirectional"))
    )
    (net (code "145") (name "unconnected-(SW4-PadCOM2)") (class "Default")
      (node (ref "SW4") (pin "COM2") (pinfunction "COM2_COM2") (pintype "bidirectional"))
    )
    (net (code "146") (name "unconnected-(SW5-PadCH1A)") (class "Default")
      (node (ref "SW5") (pin "CH1A") (pinfunction "CH1A_CH1A") (pintype "bidirectional"))
    )
    (net (code "147") (name "unconnected-(SW5-PadCH2A)") (class "Default")
      (node (ref "SW5") (pin "CH2A") (pinfunction "CH2A_CH2A") (pintype "bidirectional"))
    )
    (net (code "148") (name "unconnected-(SW6-PadCH1B)") (class "Default")
      (node (ref "SW6") (pin "CH1B") (pinfunction "CH1B_CH1B") (pintype "bidirectional"))
    )
    (net (code "149") (name "unconnected-(SW6-PadCH2B)") (class "Default")
      (node (ref "SW6") (pin "CH2B") (pinfunction "CH2B_CH2B") (pintype "bidirectional"))
    )
    (net (code "150") (name "unconnected-(SW7-PadCH2A)") (class "Default")
      (node (ref "SW7") (pin "CH2A") (pinfunction "CH2A_CH2A") (pintype "bidirectional"))
    )
    (net (code "151") (name "unconnected-(SW7-PadCH2B)") (class "Default")
      (node (ref "SW7") (pin "CH2B") (pinfunction "CH2B_CH2B") (pintype "bidirectional"))
    )
    (net (code "152") (name "unconnected-(SW7-PadCOM2)") (class "Default")
      (node (ref "SW7") (pin "COM2") (pinfunction "COM2_COM2") (pintype "bidirectional"))
    )
    (net (code "153") (name "unconnected-(U$1-Pad32)") (class "Default")
      (node (ref "U$1") (pin "32") (pinfunction "32_32") (pintype "bidirectional"))
    )
    (net (code "154") (name "unconnected-(U$1-PadAREF)") (class "Default")
      (node (ref "U$1") (pin "AREF") (pinfunction "AREF_AREF") (pintype "bidirectional"))
    )
    (net (code "155") (name "unconnected-(U$5-NC-PadP$6)") (class "Default")
      (node (ref "U$5") (pin "P$6") (pinfunction "NC_P$6") (pintype "bidirectional"))
    )
    (net (code "156") (name "unconnected-(U$8-TD-Pad4)") (class "Default")
      (node (ref "U$8") (pin "4") (pinfunction "TD_4") (pintype "bidirectional"))
    )
    (net (code "157") (name "unconnected-(U$13-ALERT-Pad2)") (class "Default")
      (node (ref "U$13") (pin "2") (pinfunction "ALERT_2") (pintype "output"))
    )
    (net (code "158") (name "unconnected-(U$14-GPIO1-Pad5)") (class "Default")
      (node (ref "U$14") (pin "5") (pinfunction "GPIO1_5") (pintype "bidirectional"))
    )
    (net (code "159") (name "unconnected-(U$14-XSHUT-Pad6)") (class "Default")
      (node (ref "U$14") (pin "6") (pinfunction "XSHUT_6") (pintype "bidirectional"))
    )
    (net (code "160") (name "unconnected-(U$15-DRDY-Pad5)") (class "Default")
      (node (ref "U$15") (pin "5") (pinfunction "DRDY_5") (pintype "bidirectional"))
    )
    (net (code "161") (name "unconnected-(U$23-EN-Pad6)") (class "Default")
      (node (ref "U$23") (pin "6") (pinfunction "EN_6") (pintype "bidirectional"))
    )
    (net (code "162") (name "unconnected-(U$23-STATE-Pad1)") (class "Default")
      (node (ref "U$23") (pin "1") (pinfunction "STATE_1") (pintype "bidirectional"))
    )
    (net (code "163") (name "unconnected-(U2-OSCIO-Pad11)") (class "Default")
      (node (ref "U2") (pin "11") (pinfunction "OSCIO_11") (pintype "bidirectional"))
    )
    (net (code "164") (name "unconnected-(U3-PadADO)") (class "Default")
      (node (ref "U3") (pin "ADO") (pinfunction "ADO_ADO") (pintype "bidirectional"))
    )
    (net (code "165") (name "unconnected-(U3-PadINT)") (class "Default")
      (node (ref "U3") (pin "INT") (pinfunction "INT_INT") (pintype "bidirectional"))
    )
    (net (code "166") (name "unconnected-(U3-PadXCL)") (class "Default")
      (node (ref "U3") (pin "XCL") (pinfunction "XCL_XCL") (pintype "bidirectional"))
    )
    (net (code "167") (name "unconnected-(U3-PadXDA)") (class "Default")
      (node (ref "U3") (pin "XDA") (pinfunction "XDA_XDA") (pintype "bidirectional"))
    )
    (net (code "168") (name "unconnected-(U4-RST-Pad4)") (class "Default")
      (node (ref "U4") (pin "4") (pinfunction "RST_4") (pintype "output"))
    )
  )
)
